# v2_1_Main.net
KiCad netlist of a schematic drawn in EAGLE
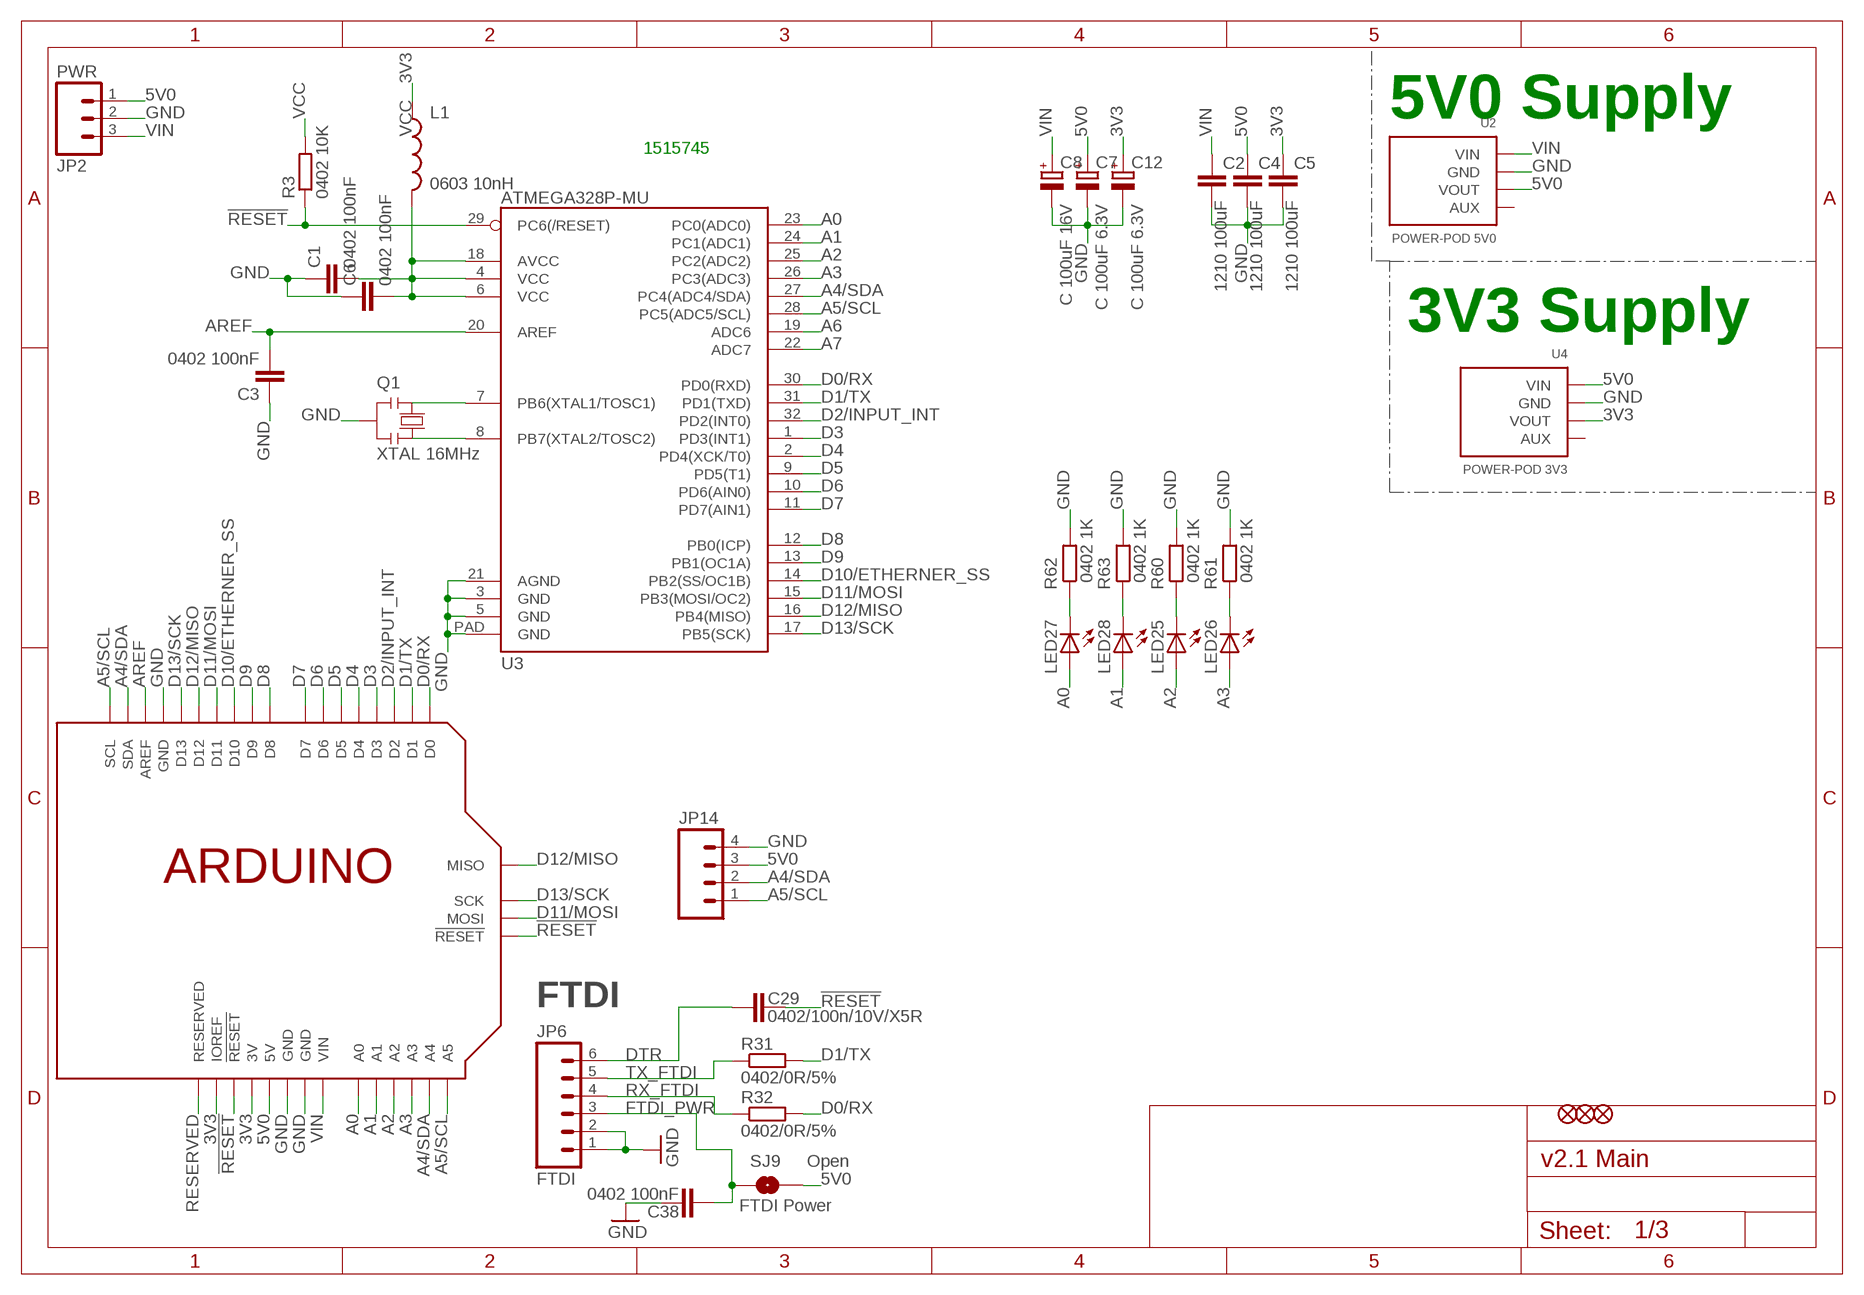
[diagram p0: schematic, sheet 1]
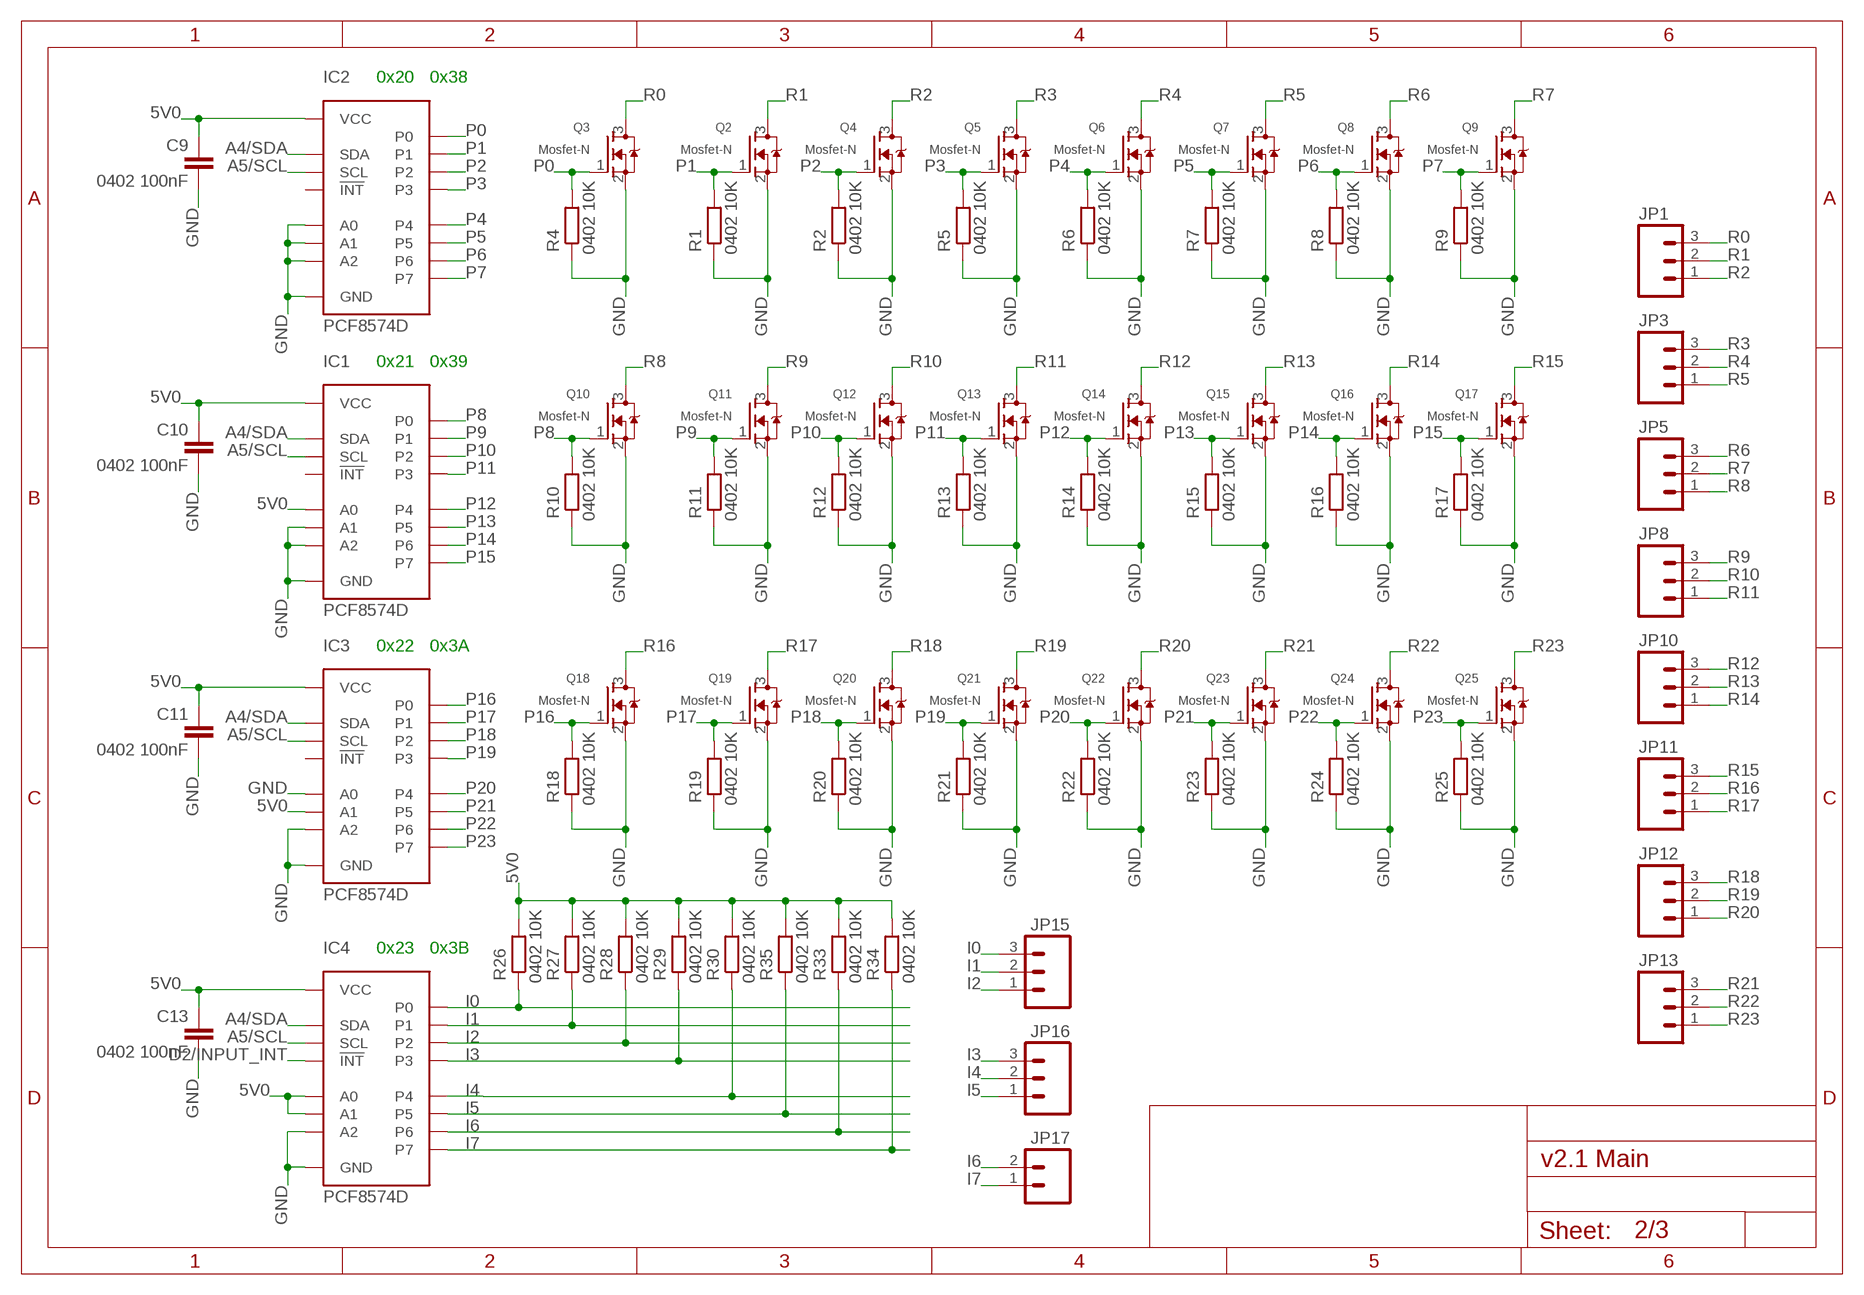
[diagram p1: schematic, sheet 2]
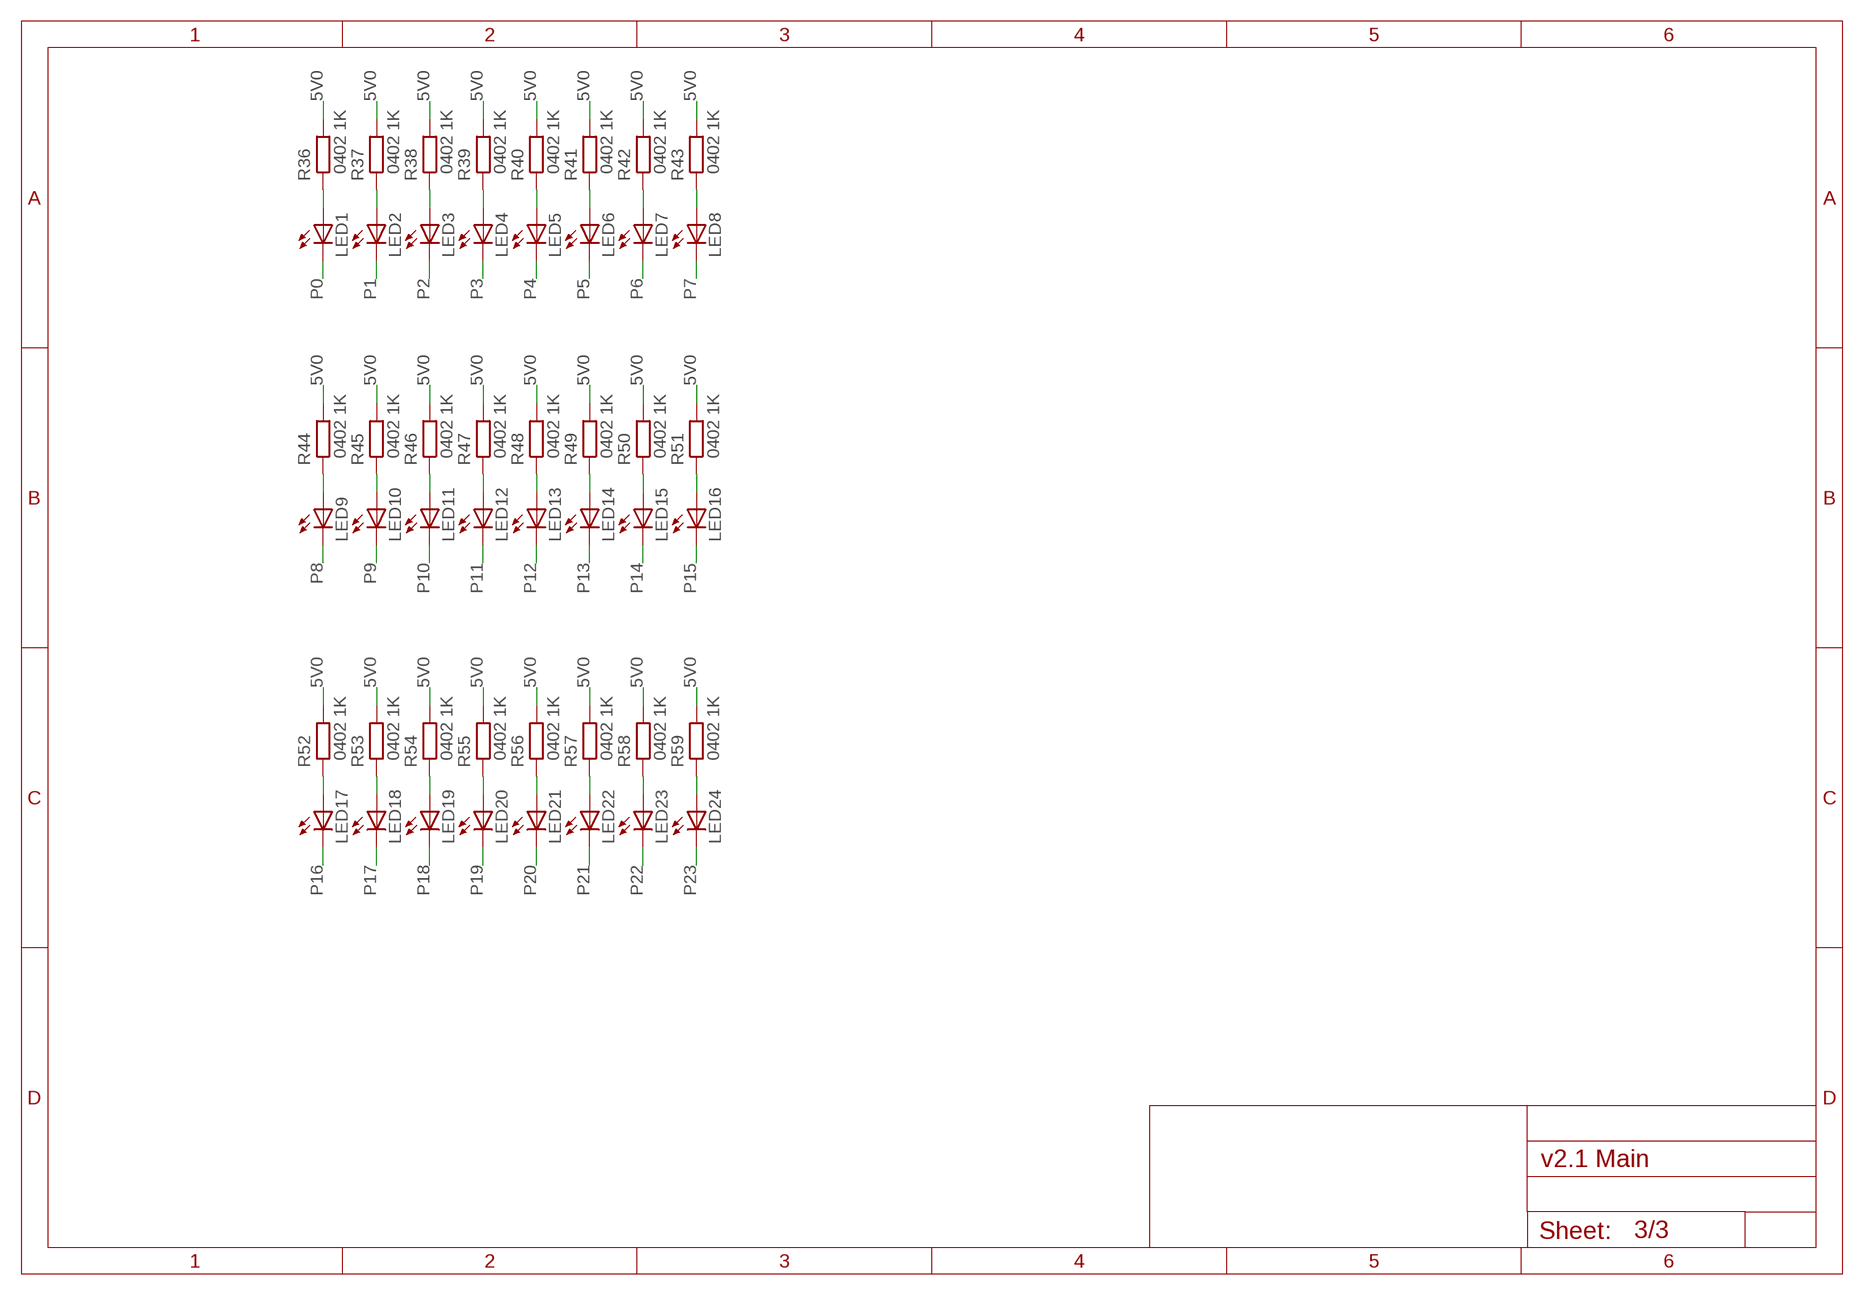
[diagram p2: schematic, sheet 3]

(export (version "E")
  (design (tool "Eeschema 10.0.6"))
  (components
    (comp (ref "LED1")
      (value "LED0805-1206")
      (footprint "eagle-import:LED-0805-1206")
      (libsource (lib "eagle-import") (part "LED0805-1206"))
    )
    (comp (ref "LED2")
      (value "LED0805-1206")
      (footprint "eagle-import:LED-0805-1206")
      (libsource (lib "eagle-import") (part "LED0805-1206"))
    )
    (comp (ref "LED3")
      (value "LED0805-1206")
      (footprint "eagle-import:LED-0805-1206")
      (libsource (lib "eagle-import") (part "LED0805-1206"))
    )
    (comp (ref "LED4")
      (value "LED0805-1206")
      (footprint "eagle-import:LED-0805-1206")
      (libsource (lib "eagle-import") (part "LED0805-1206"))
    )
    (comp (ref "LED5")
      (value "LED0805-1206")
      (footprint "eagle-import:LED-0805-1206")
      (libsource (lib "eagle-import") (part "LED0805-1206"))
    )
    (comp (ref "LED6")
      (value "LED0805-1206")
      (footprint "eagle-import:LED-0805-1206")
      (libsource (lib "eagle-import") (part "LED0805-1206"))
    )
    (comp (ref "LED7")
      (value "LED0805-1206")
      (footprint "eagle-import:LED-0805-1206")
      (libsource (lib "eagle-import") (part "LED0805-1206"))
    )
    (comp (ref "LED8")
      (value "LED0805-1206")
      (footprint "eagle-import:LED-0805-1206")
      (libsource (lib "eagle-import") (part "LED0805-1206"))
    )
    (comp (ref "LED9")
      (value "LED0805-1206")
      (footprint "eagle-import:LED-0805-1206")
      (libsource (lib "eagle-import") (part "LED0805-1206"))
    )
    (comp (ref "LED10")
      (value "LED0805-1206")
      (footprint "eagle-import:LED-0805-1206")
      (libsource (lib "eagle-import") (part "LED0805-1206"))
    )
    (comp (ref "LED11")
      (value "LED0805-1206")
      (footprint "eagle-import:LED-0805-1206")
      (libsource (lib "eagle-import") (part "LED0805-1206"))
    )
    (comp (ref "LED12")
      (value "LED0805-1206")
      (footprint "eagle-import:LED-0805-1206")
      (libsource (lib "eagle-import") (part "LED0805-1206"))
    )
    (comp (ref "LED13")
      (value "LED0805-1206")
      (footprint "eagle-import:LED-0805-1206")
      (libsource (lib "eagle-import") (part "LED0805-1206"))
    )
    (comp (ref "LED14")
      (value "LED0805-1206")
      (footprint "eagle-import:LED-0805-1206")
      (libsource (lib "eagle-import") (part "LED0805-1206"))
    )
    (comp (ref "LED15")
      (value "LED0805-1206")
      (footprint "eagle-import:LED-0805-1206")
      (libsource (lib "eagle-import") (part "LED0805-1206"))
    )
    (comp (ref "LED16")
      (value "LED0805-1206")
      (footprint "eagle-import:LED-0805-1206")
      (libsource (lib "eagle-import") (part "LED0805-1206"))
    )
    (comp (ref "LED17")
      (value "LED0805-1206")
      (footprint "eagle-import:LED-0805-1206")
      (libsource (lib "eagle-import") (part "LED0805-1206"))
    )
    (comp (ref "LED18")
      (value "LED0805-1206")
      (footprint "eagle-import:LED-0805-1206")
      (libsource (lib "eagle-import") (part "LED0805-1206"))
    )
    (comp (ref "LED19")
      (value "LED0805-1206")
      (footprint "eagle-import:LED-0805-1206")
      (libsource (lib "eagle-import") (part "LED0805-1206"))
    )
    (comp (ref "LED20")
      (value "LED0805-1206")
      (footprint "eagle-import:LED-0805-1206")
      (libsource (lib "eagle-import") (part "LED0805-1206"))
    )
    (comp (ref "LED21")
      (value "LED0805-1206")
      (footprint "eagle-import:LED-0805-1206")
      (libsource (lib "eagle-import") (part "LED0805-1206"))
    )
    (comp (ref "LED22")
      (value "LED0805-1206")
      (footprint "eagle-import:LED-0805-1206")
      (libsource (lib "eagle-import") (part "LED0805-1206"))
    )
    (comp (ref "LED23")
      (value "LED0805-1206")
      (footprint "eagle-import:LED-0805-1206")
      (libsource (lib "eagle-import") (part "LED0805-1206"))
    )
    (comp (ref "LED24")
      (value "LED0805-1206")
      (footprint "eagle-import:LED-0805-1206")
      (libsource (lib "eagle-import") (part "LED0805-1206"))
    )
    (comp (ref "R36")
      (value "0402 1K")
      (footprint "eagle-import:R0402-SMALLER")
      (libsource (lib "eagle-import") (part "R-EU_R0402-SMALLER"))
    )
    (comp (ref "R37")
      (value "0402 1K")
      (footprint "eagle-import:R0402-SMALLER")
      (libsource (lib "eagle-import") (part "R-EU_R0402-SMALLER"))
    )
    (comp (ref "R38")
      (value "0402 1K")
      (footprint "eagle-import:R0402-SMALLER")
      (libsource (lib "eagle-import") (part "R-EU_R0402-SMALLER"))
    )
    (comp (ref "R39")
      (value "0402 1K")
      (footprint "eagle-import:R0402-SMALLER")
      (libsource (lib "eagle-import") (part "R-EU_R0402-SMALLER"))
    )
    (comp (ref "R40")
      (value "0402 1K")
      (footprint "eagle-import:R0402-SMALLER")
      (libsource (lib "eagle-import") (part "R-EU_R0402-SMALLER"))
    )
    (comp (ref "R41")
      (value "0402 1K")
      (footprint "eagle-import:R0402-SMALLER")
      (libsource (lib "eagle-import") (part "R-EU_R0402-SMALLER"))
    )
    (comp (ref "R42")
      (value "0402 1K")
      (footprint "eagle-import:R0402-SMALLER")
      (libsource (lib "eagle-import") (part "R-EU_R0402-SMALLER"))
    )
    (comp (ref "R43")
      (value "0402 1K")
      (footprint "eagle-import:R0402-SMALLER")
      (libsource (lib "eagle-import") (part "R-EU_R0402-SMALLER"))
    )
    (comp (ref "R44")
      (value "0402 1K")
      (footprint "eagle-import:R0402-SMALLER")
      (libsource (lib "eagle-import") (part "R-EU_R0402-SMALLER"))
    )
    (comp (ref "R45")
      (value "0402 1K")
      (footprint "eagle-import:R0402-SMALLER")
      (libsource (lib "eagle-import") (part "R-EU_R0402-SMALLER"))
    )
    (comp (ref "R46")
      (value "0402 1K")
      (footprint "eagle-import:R0402-SMALLER")
      (libsource (lib "eagle-import") (part "R-EU_R0402-SMALLER"))
    )
    (comp (ref "R47")
      (value "0402 1K")
      (footprint "eagle-import:R0402-SMALLER")
      (libsource (lib "eagle-import") (part "R-EU_R0402-SMALLER"))
    )
    (comp (ref "R48")
      (value "0402 1K")
      (footprint "eagle-import:R0402-SMALLER")
      (libsource (lib "eagle-import") (part "R-EU_R0402-SMALLER"))
    )
    (comp (ref "R49")
      (value "0402 1K")
      (footprint "eagle-import:R0402-SMALLER")
      (libsource (lib "eagle-import") (part "R-EU_R0402-SMALLER"))
    )
    (comp (ref "R50")
      (value "0402 1K")
      (footprint "eagle-import:R0402-SMALLER")
      (libsource (lib "eagle-import") (part "R-EU_R0402-SMALLER"))
    )
    (comp (ref "R51")
      (value "0402 1K")
      (footprint "eagle-import:R0402-SMALLER")
      (libsource (lib "eagle-import") (part "R-EU_R0402-SMALLER"))
    )
    (comp (ref "R52")
      (value "0402 1K")
      (footprint "eagle-import:R0402-SMALLER")
      (libsource (lib "eagle-import") (part "R-EU_R0402-SMALLER"))
    )
    (comp (ref "R53")
      (value "0402 1K")
      (footprint "eagle-import:R0402-SMALLER")
      (libsource (lib "eagle-import") (part "R-EU_R0402-SMALLER"))
    )
    (comp (ref "R54")
      (value "0402 1K")
      (footprint "eagle-import:R0402-SMALLER")
      (libsource (lib "eagle-import") (part "R-EU_R0402-SMALLER"))
    )
    (comp (ref "R55")
      (value "0402 1K")
      (footprint "eagle-import:R0402-SMALLER")
      (libsource (lib "eagle-import") (part "R-EU_R0402-SMALLER"))
    )
    (comp (ref "R56")
      (value "0402 1K")
      (footprint "eagle-import:R0402-SMALLER")
      (libsource (lib "eagle-import") (part "R-EU_R0402-SMALLER"))
    )
    (comp (ref "R57")
      (value "0402 1K")
      (footprint "eagle-import:R0402-SMALLER")
      (libsource (lib "eagle-import") (part "R-EU_R0402-SMALLER"))
    )
    (comp (ref "R58")
      (value "0402 1K")
      (footprint "eagle-import:R0402-SMALLER")
      (libsource (lib "eagle-import") (part "R-EU_R0402-SMALLER"))
    )
    (comp (ref "R59")
      (value "0402 1K")
      (footprint "eagle-import:R0402-SMALLER")
      (libsource (lib "eagle-import") (part "R-EU_R0402-SMALLER"))
    )
    (comp (ref "C9")
      (value "0402 100nF")
      (footprint "eagle-import:C0402-SMALLER")
      (libsource (lib "eagle-import") (part "C-EUC0402-SMALLER"))
    )
    (comp (ref "C10")
      (value "0402 100nF")
      (footprint "eagle-import:C0402-SMALLER")
      (libsource (lib "eagle-import") (part "C-EUC0402-SMALLER"))
    )
    (comp (ref "C11")
      (value "0402 100nF")
      (footprint "eagle-import:C0402-SMALLER")
      (libsource (lib "eagle-import") (part "C-EUC0402-SMALLER"))
    )
    (comp (ref "C13")
      (value "0402 100nF")
      (footprint "eagle-import:C0402-SMALLER")
      (libsource (lib "eagle-import") (part "C-EUC0402-SMALLER"))
    )
    (comp (ref "IC1")
      (value "PCF8574D")
      (footprint "eagle-import:SO16-7.5MM")
      (libsource (lib "eagle-import") (part "PCF8574SO16-7/5MM"))
    )
    (comp (ref "IC2")
      (value "PCF8574D")
      (footprint "eagle-import:SO16-7.5MM")
      (libsource (lib "eagle-import") (part "PCF8574SO16-7/5MM"))
    )
    (comp (ref "IC3")
      (value "PCF8574D")
      (footprint "eagle-import:SO16-7.5MM")
      (libsource (lib "eagle-import") (part "PCF8574SO16-7/5MM"))
    )
    (comp (ref "IC4")
      (value "PCF8574D")
      (footprint "eagle-import:SO16-7.5MM")
      (libsource (lib "eagle-import") (part "PCF8574SO16-7/5MM"))
    )
    (comp (ref "JP1")
      (value "M03-SCREW-5MM")
      (footprint "eagle-import:SCREWTERMINAL-5MM-3")
      (libsource (lib "eagle-import") (part "M03-SCREW-5MM"))
    )
    (comp (ref "JP3")
      (value "M03-SCREW-5MM")
      (footprint "eagle-import:SCREWTERMINAL-5MM-3")
      (libsource (lib "eagle-import") (part "M03-SCREW-5MM"))
    )
    (comp (ref "JP5")
      (value "M03-SCREW-5MM")
      (footprint "eagle-import:SCREWTERMINAL-5MM-3")
      (libsource (lib "eagle-import") (part "M03-SCREW-5MM"))
    )
    (comp (ref "JP8")
      (value "M03-SCREW-5MM")
      (footprint "eagle-import:SCREWTERMINAL-5MM-3")
      (libsource (lib "eagle-import") (part "M03-SCREW-5MM"))
    )
    (comp (ref "JP10")
      (value "M03-SCREW-5MM")
      (footprint "eagle-import:SCREWTERMINAL-5MM-3")
      (libsource (lib "eagle-import") (part "M03-SCREW-5MM"))
    )
    (comp (ref "JP11")
      (value "M03-SCREW-5MM")
      (footprint "eagle-import:SCREWTERMINAL-5MM-3")
      (libsource (lib "eagle-import") (part "M03-SCREW-5MM"))
    )
    (comp (ref "JP12")
      (value "M03-SCREW-5MM")
      (footprint "eagle-import:SCREWTERMINAL-5MM-3")
      (libsource (lib "eagle-import") (part "M03-SCREW-5MM"))
    )
    (comp (ref "JP13")
      (value "M03-SCREW-5MM")
      (footprint "eagle-import:SCREWTERMINAL-5MM-3")
      (libsource (lib "eagle-import") (part "M03-SCREW-5MM"))
    )
    (comp (ref "JP15")
      (value "M03-SCREW-5MM")
      (footprint "eagle-import:SCREWTERMINAL-5MM-3")
      (libsource (lib "eagle-import") (part "M03-SCREW-5MM"))
    )
    (comp (ref "JP16")
      (value "M03-SCREW-5MM")
      (footprint "eagle-import:SCREWTERMINAL-5MM-3")
      (libsource (lib "eagle-import") (part "M03-SCREW-5MM"))
    )
    (comp (ref "JP17")
      (value "M025MM")
      (footprint "eagle-import:SCREWTERMINAL-5MM-2")
      (libsource (lib "eagle-import") (part "M025MM"))
    )
    (comp (ref "Q2")
      (value "Mosfet-N")
      (footprint "eagle-import:SOT23-3")
      (libsource (lib "eagle-import") (part "MOSFET-N-SOT23-SPARK"))
    )
    (comp (ref "Q3")
      (value "Mosfet-N")
      (footprint "eagle-import:SOT23-3")
      (libsource (lib "eagle-import") (part "MOSFET-N-SOT23-SPARK"))
    )
    (comp (ref "Q4")
      (value "Mosfet-N")
      (footprint "eagle-import:SOT23-3")
      (libsource (lib "eagle-import") (part "MOSFET-N-SOT23-SPARK"))
    )
    (comp (ref "Q5")
      (value "Mosfet-N")
      (footprint "eagle-import:SOT23-3")
      (libsource (lib "eagle-import") (part "MOSFET-N-SOT23-SPARK"))
    )
    (comp (ref "Q6")
      (value "Mosfet-N")
      (footprint "eagle-import:SOT23-3")
      (libsource (lib "eagle-import") (part "MOSFET-N-SOT23-SPARK"))
    )
    (comp (ref "Q7")
      (value "Mosfet-N")
      (footprint "eagle-import:SOT23-3")
      (libsource (lib "eagle-import") (part "MOSFET-N-SOT23-SPARK"))
    )
    (comp (ref "Q8")
      (value "Mosfet-N")
      (footprint "eagle-import:SOT23-3")
      (libsource (lib "eagle-import") (part "MOSFET-N-SOT23-SPARK"))
    )
    (comp (ref "Q9")
      (value "Mosfet-N")
      (footprint "eagle-import:SOT23-3")
      (libsource (lib "eagle-import") (part "MOSFET-N-SOT23-SPARK"))
    )
    (comp (ref "Q10")
      (value "Mosfet-N")
      (footprint "eagle-import:SOT23-3")
      (libsource (lib "eagle-import") (part "MOSFET-N-SOT23-SPARK"))
    )
    (comp (ref "Q11")
      (value "Mosfet-N")
      (footprint "eagle-import:SOT23-3")
      (libsource (lib "eagle-import") (part "MOSFET-N-SOT23-SPARK"))
    )
    (comp (ref "Q12")
      (value "Mosfet-N")
      (footprint "eagle-import:SOT23-3")
      (libsource (lib "eagle-import") (part "MOSFET-N-SOT23-SPARK"))
    )
    (comp (ref "Q13")
      (value "Mosfet-N")
      (footprint "eagle-import:SOT23-3")
      (libsource (lib "eagle-import") (part "MOSFET-N-SOT23-SPARK"))
    )
    (comp (ref "Q14")
      (value "Mosfet-N")
      (footprint "eagle-import:SOT23-3")
      (libsource (lib "eagle-import") (part "MOSFET-N-SOT23-SPARK"))
    )
    (comp (ref "Q15")
      (value "Mosfet-N")
      (footprint "eagle-import:SOT23-3")
      (libsource (lib "eagle-import") (part "MOSFET-N-SOT23-SPARK"))
    )
    (comp (ref "Q16")
      (value "Mosfet-N")
      (footprint "eagle-import:SOT23-3")
      (libsource (lib "eagle-import") (part "MOSFET-N-SOT23-SPARK"))
    )
    (comp (ref "Q17")
      (value "Mosfet-N")
      (footprint "eagle-import:SOT23-3")
      (libsource (lib "eagle-import") (part "MOSFET-N-SOT23-SPARK"))
    )
    (comp (ref "Q18")
      (value "Mosfet-N")
      (footprint "eagle-import:SOT23-3")
      (libsource (lib "eagle-import") (part "MOSFET-N-SOT23-SPARK"))
    )
    (comp (ref "Q19")
      (value "Mosfet-N")
      (footprint "eagle-import:SOT23-3")
      (libsource (lib "eagle-import") (part "MOSFET-N-SOT23-SPARK"))
    )
    (comp (ref "Q20")
      (value "Mosfet-N")
      (footprint "eagle-import:SOT23-3")
      (libsource (lib "eagle-import") (part "MOSFET-N-SOT23-SPARK"))
    )
    (comp (ref "Q21")
      (value "Mosfet-N")
      (footprint "eagle-import:SOT23-3")
      (libsource (lib "eagle-import") (part "MOSFET-N-SOT23-SPARK"))
    )
    (comp (ref "Q22")
      (value "Mosfet-N")
      (footprint "eagle-import:SOT23-3")
      (libsource (lib "eagle-import") (part "MOSFET-N-SOT23-SPARK"))
    )
    (comp (ref "Q23")
      (value "Mosfet-N")
      (footprint "eagle-import:SOT23-3")
      (libsource (lib "eagle-import") (part "MOSFET-N-SOT23-SPARK"))
    )
    (comp (ref "Q24")
      (value "Mosfet-N")
      (footprint "eagle-import:SOT23-3")
      (libsource (lib "eagle-import") (part "MOSFET-N-SOT23-SPARK"))
    )
    (comp (ref "Q25")
      (value "Mosfet-N")
      (footprint "eagle-import:SOT23-3")
      (libsource (lib "eagle-import") (part "MOSFET-N-SOT23-SPARK"))
    )
    (comp (ref "R1")
      (value "0402 10K")
      (footprint "eagle-import:R0402-SMALLER")
      (libsource (lib "eagle-import") (part "R-EU_R0402-SMALLER"))
    )
    (comp (ref "R2")
      (value "0402 10K")
      (footprint "eagle-import:R0402-SMALLER")
      (libsource (lib "eagle-import") (part "R-EU_R0402-SMALLER"))
    )
    (comp (ref "R4")
      (value "0402 10K")
      (footprint "eagle-import:R0402-SMALLER")
      (libsource (lib "eagle-import") (part "R-EU_R0402-SMALLER"))
    )
    (comp (ref "R5")
      (value "0402 10K")
      (footprint "eagle-import:R0402-SMALLER")
      (libsource (lib "eagle-import") (part "R-EU_R0402-SMALLER"))
    )
    (comp (ref "R6")
      (value "0402 10K")
      (footprint "eagle-import:R0402-SMALLER")
      (libsource (lib "eagle-import") (part "R-EU_R0402-SMALLER"))
    )
    (comp (ref "R7")
      (value "0402 10K")
      (footprint "eagle-import:R0402-SMALLER")
      (libsource (lib "eagle-import") (part "R-EU_R0402-SMALLER"))
    )
    (comp (ref "R8")
      (value "0402 10K")
      (footprint "eagle-import:R0402-SMALLER")
      (libsource (lib "eagle-import") (part "R-EU_R0402-SMALLER"))
    )
    (comp (ref "R9")
      (value "0402 10K")
      (footprint "eagle-import:R0402-SMALLER")
      (libsource (lib "eagle-import") (part "R-EU_R0402-SMALLER"))
    )
    (comp (ref "R10")
      (value "0402 10K")
      (footprint "eagle-import:R0402-SMALLER")
      (libsource (lib "eagle-import") (part "R-EU_R0402-SMALLER"))
    )
    (comp (ref "R11")
      (value "0402 10K")
      (footprint "eagle-import:R0402-SMALLER")
      (libsource (lib "eagle-import") (part "R-EU_R0402-SMALLER"))
    )
    (comp (ref "R12")
      (value "0402 10K")
      (footprint "eagle-import:R0402-SMALLER")
      (libsource (lib "eagle-import") (part "R-EU_R0402-SMALLER"))
    )
    (comp (ref "R13")
      (value "0402 10K")
      (footprint "eagle-import:R0402-SMALLER")
      (libsource (lib "eagle-import") (part "R-EU_R0402-SMALLER"))
    )
    (comp (ref "R14")
      (value "0402 10K")
      (footprint "eagle-import:R0402-SMALLER")
      (libsource (lib "eagle-import") (part "R-EU_R0402-SMALLER"))
    )
    (comp (ref "R15")
      (value "0402 10K")
      (footprint "eagle-import:R0402-SMALLER")
      (libsource (lib "eagle-import") (part "R-EU_R0402-SMALLER"))
    )
    (comp (ref "R16")
      (value "0402 10K")
      (footprint "eagle-import:R0402-SMALLER")
      (libsource (lib "eagle-import") (part "R-EU_R0402-SMALLER"))
    )
    (comp (ref "R17")
      (value "0402 10K")
      (footprint "eagle-import:R0402-SMALLER")
      (libsource (lib "eagle-import") (part "R-EU_R0402-SMALLER"))
    )
    (comp (ref "R18")
      (value "0402 10K")
      (footprint "eagle-import:R0402-SMALLER")
      (libsource (lib "eagle-import") (part "R-EU_R0402-SMALLER"))
    )
    (comp (ref "R19")
      (value "0402 10K")
      (footprint "eagle-import:R0402-SMALLER")
      (libsource (lib "eagle-import") (part "R-EU_R0402-SMALLER"))
    )
    (comp (ref "R20")
      (value "0402 10K")
      (footprint "eagle-import:R0402-SMALLER")
      (libsource (lib "eagle-import") (part "R-EU_R0402-SMALLER"))
    )
    (comp (ref "R21")
      (value "0402 10K")
      (footprint "eagle-import:R0402-SMALLER")
      (libsource (lib "eagle-import") (part "R-EU_R0402-SMALLER"))
    )
    (comp (ref "R22")
      (value "0402 10K")
      (footprint "eagle-import:R0402-SMALLER")
      (libsource (lib "eagle-import") (part "R-EU_R0402-SMALLER"))
    )
    (comp (ref "R23")
      (value "0402 10K")
      (footprint "eagle-import:R0402-SMALLER")
      (libsource (lib "eagle-import") (part "R-EU_R0402-SMALLER"))
    )
    (comp (ref "R24")
      (value "0402 10K")
      (footprint "eagle-import:R0402-SMALLER")
      (libsource (lib "eagle-import") (part "R-EU_R0402-SMALLER"))
    )
    (comp (ref "R25")
      (value "0402 10K")
      (footprint "eagle-import:R0402-SMALLER")
      (libsource (lib "eagle-import") (part "R-EU_R0402-SMALLER"))
    )
    (comp (ref "R26")
      (value "0402 10K")
      (footprint "eagle-import:R0402-SMALLER")
      (libsource (lib "eagle-import") (part "R-EU_R0402-SMALLER"))
    )
    (comp (ref "R27")
      (value "0402 10K")
      (footprint "eagle-import:R0402-SMALLER")
      (libsource (lib "eagle-import") (part "R-EU_R0402-SMALLER"))
    )
    (comp (ref "R28")
      (value "0402 10K")
      (footprint "eagle-import:R0402-SMALLER")
      (libsource (lib "eagle-import") (part "R-EU_R0402-SMALLER"))
    )
    (comp (ref "R29")
      (value "0402 10K")
      (footprint "eagle-import:R0402-SMALLER")
      (libsource (lib "eagle-import") (part "R-EU_R0402-SMALLER"))
    )
    (comp (ref "R30")
      (value "0402 10K")
      (footprint "eagle-import:R0402-SMALLER")
      (libsource (lib "eagle-import") (part "R-EU_R0402-SMALLER"))
    )
    (comp (ref "R33")
      (value "0402 10K")
      (footprint "eagle-import:R0402-SMALLER")
      (libsource (lib "eagle-import") (part "R-EU_R0402-SMALLER"))
    )
    (comp (ref "R34")
      (value "0402 10K")
      (footprint "eagle-import:R0402-SMALLER")
      (libsource (lib "eagle-import") (part "R-EU_R0402-SMALLER"))
    )
    (comp (ref "R35")
      (value "0402 10K")
      (footprint "eagle-import:R0402-SMALLER")
      (libsource (lib "eagle-import") (part "R-EU_R0402-SMALLER"))
    )
    (comp (ref "C1")
      (value "0402 100nF")
      (footprint "eagle-import:C0402-SMALLER")
      (libsource (lib "eagle-import") (part "C-EUC0402-SMALLER"))
    )
    (comp (ref "C2")
      (value "1210 100uF")
      (footprint "eagle-import:C1210")
      (libsource (lib "eagle-import") (part "C-EUC1210"))
    )
    (comp (ref "C3")
      (value "0402 100nF")
      (footprint "eagle-import:C0402-SMALLER")
      (libsource (lib "eagle-import") (part "C-EUC0402-SMALLER"))
    )
    (comp (ref "C4")
      (value "1210 100uF")
      (footprint "eagle-import:C1210")
      (libsource (lib "eagle-import") (part "C-EUC1210"))
    )
    (comp (ref "C5")
      (value "1210 100uF")
      (footprint "eagle-import:C1210")
      (libsource (lib "eagle-import") (part "C-EUC1210"))
    )
    (comp (ref "C6")
      (value "0402 100nF")
      (footprint "eagle-import:C0402-SMALLER")
      (libsource (lib "eagle-import") (part "C-EUC0402-SMALLER"))
    )
    (comp (ref "C7")
      (value "C 100uF 6.3V")
      (footprint "eagle-import:PANASONIC_C")
      (libsource (lib "eagle-import") (part "CPOL-EUC"))
    )
    (comp (ref "C8")
      (value "C 100uF 16V")
      (footprint "eagle-import:PANASONIC_C")
      (libsource (lib "eagle-import") (part "CPOL-EUC"))
    )
    (comp (ref "C12")
      (value "C 100uF 6.3V")
      (footprint "eagle-import:PANASONIC_C")
      (libsource (lib "eagle-import") (part "CPOL-EUC"))
    )
    (comp (ref "C29")
      (value "0402/100n/10V/X5R")
      (footprint "eagle-import:C0402-ARDUINO-ROUND")
      (libsource (lib "eagle-import") (part "TiLDA Mk2 Parts_C-EUC0402-ARDUINO-ROUND"))
    )
    (comp (ref "C38")
      (value "0402 100nF")
      (footprint "eagle-import:C0402-SMALLER")
      (libsource (lib "eagle-import") (part "TiLDA Mk2 Parts_C-EUC0402-SMALLER"))
    )
    (comp (ref "JP2")
      (value "PWR")
      (footprint "eagle-import:SCREWTERMINAL-5MM-3")
      (libsource (lib "eagle-import") (part "M03-SCREW-5MM"))
    )
    (comp (ref "JP4")
      (value "FIDUCIAL1X2.5-STOP")
      (footprint "eagle-import:FIDUCIAL-1X2.5-STOP")
      (libsource (lib "eagle-import") (part "FIDUCIAL1X2.5-STOP"))
    )
    (comp (ref "JP6")
      (value "FTDI")
      (footprint "eagle-import:1X06")
      (libsource (lib "eagle-import") (part "M06SIP"))
    )
    (comp (ref "JP7")
      (value "FIDUCIAL1X2.5-STOP")
      (footprint "eagle-import:FIDUCIAL-1X2.5-STOP")
      (libsource (lib "eagle-import") (part "FIDUCIAL1X2.5-STOP"))
    )
    (comp (ref "JP9")
      (value "FIDUCIAL1X2.5-STOP")
      (footprint "eagle-import:FIDUCIAL-1X2.5-STOP")
      (libsource (lib "eagle-import") (part "FIDUCIAL1X2.5-STOP"))
    )
    (comp (ref "JP14")
      (value "M04PTH")
      (footprint "eagle-import:1X04")
      (libsource (lib "eagle-import") (part "M04PTH"))
    )
    (comp (ref "L1")
      (value "0603 10nH")
      (footprint "eagle-import:C0603K-SMALL")
      (libsource (lib "eagle-import") (part "INDUCTOR0603K-SMALL"))
    )
    (comp (ref "LED25")
      (value "LED0805-1206")
      (footprint "eagle-import:LED-0805-1206")
      (libsource (lib "eagle-import") (part "LED0805-1206"))
    )
    (comp (ref "LED26")
      (value "LED0805-1206")
      (footprint "eagle-import:LED-0805-1206")
      (libsource (lib "eagle-import") (part "LED0805-1206"))
    )
    (comp (ref "LED27")
      (value "LED0805-1206")
      (footprint "eagle-import:LED-0805-1206")
      (libsource (lib "eagle-import") (part "LED0805-1206"))
    )
    (comp (ref "LED28")
      (value "LED0805-1206")
      (footprint "eagle-import:LED-0805-1206")
      (libsource (lib "eagle-import") (part "LED0805-1206"))
    )
    (comp (ref "Q1")
      (value "XTAL 16MHz")
      (footprint "eagle-import:RESONATOR")
      (libsource (lib "eagle-import") (part "RESONATORMU"))
    )
    (comp (ref "R3")
      (value "0402 10K")
      (footprint "eagle-import:R0402-SMALLER")
      (libsource (lib "eagle-import") (part "R-EU_R0402-SMALLER"))
    )
    (comp (ref "R31")
      (value "0402/0R/5%")
      (footprint "eagle-import:R0402-ARDUINO-ROUND")
      (libsource (lib "eagle-import") (part "TiLDA Mk2 Parts_R-EU_R0402-ARDUINO-ROUND"))
    )
    (comp (ref "R32")
      (value "0402/0R/5%")
      (footprint "eagle-import:R0402-ARDUINO-ROUND")
      (libsource (lib "eagle-import") (part "TiLDA Mk2 Parts_R-EU_R0402-ARDUINO-ROUND"))
    )
    (comp (ref "R60")
      (value "0402 1K")
      (footprint "eagle-import:R0402-SMALLER")
      (libsource (lib "eagle-import") (part "R-EU_R0402-SMALLER"))
    )
    (comp (ref "R61")
      (value "0402 1K")
      (footprint "eagle-import:R0402-SMALLER")
      (libsource (lib "eagle-import") (part "R-EU_R0402-SMALLER"))
    )
    (comp (ref "R62")
      (value "0402 1K")
      (footprint "eagle-import:R0402-SMALLER")
      (libsource (lib "eagle-import") (part "R-EU_R0402-SMALLER"))
    )
    (comp (ref "R63")
      (value "0402 1K")
      (footprint "eagle-import:R0402-SMALLER")
      (libsource (lib "eagle-import") (part "R-EU_R0402-SMALLER"))
    )
    (comp (ref "SJ9")
      (value "FTDI Power")
      (footprint "eagle-import:SJ_2S-TRACE")
      (libsource (lib "eagle-import") (part "SOLDERJUMPERTRACE"))
    )
    (comp (ref "U1")
      (value "ARDUINOSPI-REFRENCE")
      (footprint "eagle-import:ARDUINOR3-LWKTXT-REF-SPI")
      (libsource (lib "eagle-import") (part "ARDUINOSPI-REFRENCE"))
    )
    (comp (ref "U2")
      (value "POWER-POD 5V0")
      (footprint "eagle-import:POWER-POD-LANDING")
      (libsource (lib "eagle-import") (part "POWER-POD"))
    )
    (comp (ref "U3")
      (value "ATMEGA328P-MU")
      (footprint "eagle-import:MLF32-SHORT-CREAM")
      (libsource (lib "eagle-import") (part "ATMEGA328-MLF-SHORT"))
    )
    (comp (ref "U4")
      (value "POWER-POD 3V3")
      (footprint "eagle-import:POWER-POD-LANDING")
      (libsource (lib "eagle-import") (part "POWER-POD"))
    )
  )
  (nets
    (net (code "1") (name "3V3") (class "Default")
      (node (ref "C12") (pin "+") (pinfunction "+_+") (pintype "passive"))
      (node (ref "C5") (pin "1") (pinfunction "1_1") (pintype "passive"))
      (node (ref "L1") (pin "1") (pinfunction "1_1") (pintype "passive"))
      (node (ref "U1") (pin "3V") (pinfunction "3V_3V") (pintype "power_in"))
      (node (ref "U1") (pin "IOREF") (pinfunction "IOREF_IOREF") (pintype "output"))
      (node (ref "U4") (pin "3") (pinfunction "VOUT_3") (pintype "bidirectional"))
    )
    (net (code "2") (name "5V0") (class "Default")
      (node (ref "C10") (pin "1") (pinfunction "1_1") (pintype "passive"))
      (node (ref "C11") (pin "1") (pinfunction "1_1") (pintype "passive"))
      (node (ref "C13") (pin "1") (pinfunction "1_1") (pintype "passive"))
      (node (ref "C4") (pin "1") (pinfunction "1_1") (pintype "passive"))
      (node (ref "C7") (pin "+") (pinfunction "+_+") (pintype "passive"))
      (node (ref "C9") (pin "1") (pinfunction "1_1") (pintype "passive"))
      (node (ref "IC1") (pin "1") (pinfunction "A0_1") (pintype "bidirectional"))
      (node (ref "IC1") (pin "16") (pinfunction "VCC_16") (pintype "bidirectional"))
      (node (ref "IC2") (pin "16") (pinfunction "VCC_16") (pintype "bidirectional"))
      (node (ref "IC3") (pin "16") (pinfunction "VCC_16") (pintype "bidirectional"))
      (node (ref "IC3") (pin "2") (pinfunction "A1_2") (pintype "bidirectional"))
      (node (ref "IC4") (pin "1") (pinfunction "A0_1") (pintype "bidirectional"))
      (node (ref "IC4") (pin "16") (pinfunction "VCC_16") (pintype "bidirectional"))
      (node (ref "IC4") (pin "2") (pinfunction "A1_2") (pintype "bidirectional"))
      (node (ref "JP14") (pin "3") (pinfunction "3_3") (pintype "passive"))
      (node (ref "JP2") (pin "1") (pinfunction "1_1") (pintype "passive"))
      (node (ref "R26") (pin "2") (pinfunction "2_2") (pintype "passive"))
      (node (ref "R27") (pin "2") (pinfunction "2_2") (pintype "passive"))
      (node (ref "R28") (pin "2") (pinfunction "2_2") (pintype "passive"))
      (node (ref "R29") (pin "2") (pinfunction "2_2") (pintype "passive"))
      (node (ref "R30") (pin "2") (pinfunction "2_2") (pintype "passive"))
      (node (ref "R33") (pin "2") (pinfunction "2_2") (pintype "passive"))
      (node (ref "R34") (pin "2") (pinfunction "2_2") (pintype "passive"))
      (node (ref "R35") (pin "2") (pinfunction "2_2") (pintype "passive"))
      (node (ref "R36") (pin "2") (pinfunction "2_2") (pintype "passive"))
      (node (ref "R37") (pin "2") (pinfunction "2_2") (pintype "passive"))
      (node (ref "R38") (pin "2") (pinfunction "2_2") (pintype "passive"))
      (node (ref "R39") (pin "2") (pinfunction "2_2") (pintype "passive"))
      (node (ref "R40") (pin "2") (pinfunction "2_2") (pintype "passive"))
      (node (ref "R41") (pin "2") (pinfunction "2_2") (pintype "passive"))
      (node (ref "R42") (pin "2") (pinfunction "2_2") (pintype "passive"))
      (node (ref "R43") (pin "2") (pinfunction "2_2") (pintype "passive"))
      (node (ref "R44") (pin "2") (pinfunction "2_2") (pintype "passive"))
      (node (ref "R45") (pin "2") (pinfunction "2_2") (pintype "passive"))
      (node (ref "R46") (pin "2") (pinfunction "2_2") (pintype "passive"))
      (node (ref "R47") (pin "2") (pinfunction "2_2") (pintype "passive"))
      (node (ref "R48") (pin "2") (pinfunction "2_2") (pintype "passive"))
      (node (ref "R49") (pin "2") (pinfunction "2_2") (pintype "passive"))
      (node (ref "R50") (pin "2") (pinfunction "2_2") (pintype "passive"))
      (node (ref "R51") (pin "2") (pinfunction "2_2") (pintype "passive"))
      (node (ref "R52") (pin "2") (pinfunction "2_2") (pintype "passive"))
      (node (ref "R53") (pin "2") (pinfunction "2_2") (pintype "passive"))
      (node (ref "R54") (pin "2") (pinfunction "2_2") (pintype "passive"))
      (node (ref "R55") (pin "2") (pinfunction "2_2") (pintype "passive"))
      (node (ref "R56") (pin "2") (pinfunction "2_2") (pintype "passive"))
      (node (ref "R57") (pin "2") (pinfunction "2_2") (pintype "passive"))
      (node (ref "R58") (pin "2") (pinfunction "2_2") (pintype "passive"))
      (node (ref "R59") (pin "2") (pinfunction "2_2") (pintype "passive"))
      (node (ref "SJ9") (pin "2") (pinfunction "2_2") (pintype "passive"))
      (node (ref "U1") (pin "5V") (pinfunction "5V_5V") (pintype "power_in"))
      (node (ref "U1") (pin "5V@ISP") (pinfunction "5V_5V@ISP") (pintype "power_in"))
      (node (ref "U2") (pin "3") (pinfunction "VOUT_3") (pintype "bidirectional"))
      (node (ref "U4") (pin "1") (pinfunction "VIN_1") (pintype "bidirectional"))
    )
    (net (code "3") (name "A0") (class "Default")
      (node (ref "LED27") (pin "A") (pinfunction "A_A") (pintype "passive"))
      (node (ref "U1") (pin "A0") (pinfunction "A0_A0") (pintype "bidirectional"))
      (node (ref "U3") (pin "23") (pinfunction "PC0(ADC0)_23") (pintype "bidirectional"))
    )
    (net (code "4") (name "A1") (class "Default")
      (node (ref "LED28") (pin "A") (pinfunction "A_A") (pintype "passive"))
      (node (ref "U1") (pin "A1") (pinfunction "A1_A1") (pintype "bidirectional"))
      (node (ref "U3") (pin "24") (pinfunction "PC1(ADC1)_24") (pintype "bidirectional"))
    )
    (net (code "5") (name "A2") (class "Default")
      (node (ref "LED25") (pin "A") (pinfunction "A_A") (pintype "passive"))
      (node (ref "U1") (pin "A2") (pinfunction "A2_A2") (pintype "bidirectional"))
      (node (ref "U3") (pin "25") (pinfunction "PC2(ADC2)_25") (pintype "bidirectional"))
    )
    (net (code "6") (name "A3") (class "Default")
      (node (ref "LED26") (pin "A") (pinfunction "A_A") (pintype "passive"))
      (node (ref "U1") (pin "A3") (pinfunction "A3_A3") (pintype "bidirectional"))
      (node (ref "U3") (pin "26") (pinfunction "PC3(ADC3)_26") (pintype "bidirectional"))
    )
    (net (code "7") (name "A4{slash}SDA") (class "Default")
      (node (ref "IC1") (pin "15") (pinfunction "SDA_15") (pintype "bidirectional"))
      (node (ref "IC2") (pin "15") (pinfunction "SDA_15") (pintype "bidirectional"))
      (node (ref "IC3") (pin "15") (pinfunction "SDA_15") (pintype "bidirectional"))
      (node (ref "IC4") (pin "15") (pinfunction "SDA_15") (pintype "bidirectional"))
      (node (ref "JP14") (pin "2") (pinfunction "2_2") (pintype "passive"))
      (node (ref "U1") (pin "A4") (pinfunction "A4_A4") (pintype "bidirectional"))
      (node (ref "U1") (pin "SDA") (pinfunction "SDA_SDA") (pintype "bidirectional"))
      (node (ref "U3") (pin "27") (pinfunction "PC4(ADC4/SDA)_27") (pintype "bidirectional"))
    )
    (net (code "8") (name "A5{slash}SCL") (class "Default")
      (node (ref "IC1") (pin "14") (pinfunction "SCL_14") (pintype "bidirectional"))
      (node (ref "IC2") (pin "14") (pinfunction "SCL_14") (pintype "bidirectional"))
      (node (ref "IC3") (pin "14") (pinfunction "SCL_14") (pintype "bidirectional"))
      (node (ref "IC4") (pin "14") (pinfunction "SCL_14") (pintype "bidirectional"))
      (node (ref "JP14") (pin "1") (pinfunction "1_1") (pintype "passive"))
      (node (ref "U1") (pin "A5") (pinfunction "A5_A5") (pintype "bidirectional"))
      (node (ref "U1") (pin "SCL") (pinfunction "SCL_SCL") (pintype "bidirectional"))
      (node (ref "U3") (pin "28") (pinfunction "PC5(ADC5/SCL)_28") (pintype "bidirectional"))
    )
    (net (code "9") (name "A6") (class "Default")
      (node (ref "U3") (pin "19") (pinfunction "ADC6_19") (pintype "bidirectional"))
    )
    (net (code "10") (name "A7") (class "Default")
      (node (ref "U3") (pin "22") (pinfunction "ADC7_22") (pintype "bidirectional"))
    )
    (net (code "11") (name "AREF") (class "Default")
      (node (ref "C3") (pin "2") (pinfunction "2_2") (pintype "passive"))
      (node (ref "U1") (pin "AREF") (pinfunction "AREF_AREF") (pintype "bidirectional"))
      (node (ref "U3") (pin "20") (pinfunction "AREF_20") (pintype "bidirectional"))
    )
    (net (code "12") (name "D0{slash}RX") (class "Default")
      (node (ref "R32") (pin "2") (pinfunction "2_2") (pintype "passive"))
      (node (ref "U1") (pin "D0") (pinfunction "D0_D0") (pintype "bidirectional"))
      (node (ref "U3") (pin "30") (pinfunction "PD0(RXD)_30") (pintype "bidirectional"))
    )
    (net (code "13") (name "D1{slash}TX") (class "Default")
      (node (ref "R31") (pin "2") (pinfunction "2_2") (pintype "passive"))
      (node (ref "U1") (pin "D1") (pinfunction "D1_D1") (pintype "bidirectional"))
      (node (ref "U3") (pin "31") (pinfunction "PD1(TXD)_31") (pintype "bidirectional"))
    )
    (net (code "14") (name "D2{slash}INPUT_INT") (class "Default")
      (node (ref "IC4") (pin "13") (pinfunction "~{INT}_13") (pintype "bidirectional"))
      (node (ref "U1") (pin "D2") (pinfunction "D2_D2") (pintype "bidirectional"))
      (node (ref "U3") (pin "32") (pinfunction "PD2(INT0)_32") (pintype "bidirectional"))
    )
    (net (code "15") (name "D3") (class "Default")
      (node (ref "U1") (pin "D3") (pinfunction "D3_D3") (pintype "bidirectional"))
      (node (ref "U3") (pin "1") (pinfunction "PD3(INT1)_1") (pintype "bidirectional"))
    )
    (net (code "16") (name "D4") (class "Default")
      (node (ref "U1") (pin "D4") (pinfunction "D4_D4") (pintype "bidirectional"))
      (node (ref "U3") (pin "2") (pinfunction "PD4(XCK/T0)_2") (pintype "bidirectional"))
    )
    (net (code "17") (name "D5") (class "Default")
      (node (ref "U1") (pin "D5") (pinfunction "D5_D5") (pintype "bidirectional"))
      (node (ref "U3") (pin "9") (pinfunction "PD5(T1)_9") (pintype "bidirectional"))
    )
    (net (code "18") (name "D6") (class "Default")
      (node (ref "U1") (pin "D6") (pinfunction "D6_D6") (pintype "bidirectional"))
      (node (ref "U3") (pin "10") (pinfunction "PD6(AIN0)_10") (pintype "bidirectional"))
    )
    (net (code "19") (name "D7") (class "Default")
      (node (ref "U1") (pin "D7") (pinfunction "D7_D7") (pintype "bidirectional"))
      (node (ref "U3") (pin "11") (pinfunction "PD7(AIN1)_11") (pintype "bidirectional"))
    )
    (net (code "20") (name "D8") (class "Default")
      (node (ref "U1") (pin "D8") (pinfunction "D8_D8") (pintype "bidirectional"))
      (node (ref "U3") (pin "12") (pinfunction "PB0(ICP)_12") (pintype "bidirectional"))
    )
    (net (code "21") (name "D9") (class "Default")
      (node (ref "U1") (pin "D9") (pinfunction "D9_D9") (pintype "bidirectional"))
      (node (ref "U3") (pin "13") (pinfunction "PB1(OC1A)_13") (pintype "bidirectional"))
    )
    (net (code "22") (name "D10{slash}ETHERNER_SS") (class "Default")
      (node (ref "U1") (pin "D10") (pinfunction "D10_D10") (pintype "bidirectional"))
      (node (ref "U3") (pin "14") (pinfunction "PB2(SS/OC1B)_14") (pintype "bidirectional"))
    )
    (net (code "23") (name "D11{slash}MOSI") (class "Default")
      (node (ref "U1") (pin "D11") (pinfunction "D11_D11") (pintype "bidirectional"))
      (node (ref "U1") (pin "MOSI") (pinfunction "MOSI_MOSI") (pintype "bidirectional"))
      (node (ref "U3") (pin "15") (pinfunction "PB3(MOSI/OC2)_15") (pintype "bidirectional"))
    )
    (net (code "24") (name "D12{slash}MISO") (class "Default")
      (node (ref "U1") (pin "D12") (pinfunction "D12_D12") (pintype "bidirectional"))
      (node (ref "U1") (pin "MISO") (pinfunction "MISO_MISO") (pintype "bidirectional"))
      (node (ref "U3") (pin "16") (pinfunction "PB4(MISO)_16") (pintype "bidirectional"))
    )
    (net (code "25") (name "D13{slash}SCK") (class "Default")
      (node (ref "U1") (pin "D13") (pinfunction "D13_D13") (pintype "bidirectional"))
      (node (ref "U1") (pin "SCK") (pinfunction "SCK_SCK") (pintype "bidirectional"))
      (node (ref "U3") (pin "17") (pinfunction "PB5(SCK)_17") (pintype "bidirectional"))
    )
    (net (code "26") (name "DTR") (class "Default")
      (node (ref "C29") (pin "2") (pinfunction "2_2") (pintype "passive"))
      (node (ref "JP6") (pin "6") (pinfunction "6_6") (pintype "passive"))
    )
    (net (code "27") (name "FTDI_PWR") (class "Default")
      (node (ref "C38") (pin "2") (pinfunction "2_2") (pintype "passive"))
      (node (ref "JP6") (pin "3") (pinfunction "3_3") (pintype "passive"))
      (node (ref "SJ9") (pin "1") (pinfunction "1_1") (pintype "passive"))
    )
    (net (code "28") (name "GND") (class "Default")
      (node (ref "C1") (pin "1") (pinfunction "1_1") (pintype "passive"))
      (node (ref "C10") (pin "2") (pinfunction "2_2") (pintype "passive"))
      (node (ref "C11") (pin "2") (pinfunction "2_2") (pintype "passive"))
      (node (ref "C12") (pin "-") (pinfunction "-_-") (pintype "passive"))
      (node (ref "C13") (pin "2") (pinfunction "2_2") (pintype "passive"))
      (node (ref "C2") (pin "2") (pinfunction "2_2") (pintype "passive"))
      (node (ref "C3") (pin "1") (pinfunction "1_1") (pintype "passive"))
      (node (ref "C38") (pin "1") (pinfunction "1_1") (pintype "passive"))
      (node (ref "C4") (pin "2") (pinfunction "2_2") (pintype "passive"))
      (node (ref "C5") (pin "2") (pinfunction "2_2") (pintype "passive"))
      (node (ref "C6") (pin "1") (pinfunction "1_1") (pintype "passive"))
      (node (ref "C7") (pin "-") (pinfunction "-_-") (pintype "passive"))
      (node (ref "C8") (pin "-") (pinfunction "-_-") (pintype "passive"))
      (node (ref "C9") (pin "2") (pinfunction "2_2") (pintype "passive"))
      (node (ref "IC1") (pin "2") (pinfunction "A1_2") (pintype "bidirectional"))
      (node (ref "IC1") (pin "3") (pinfunction "A2_3") (pintype "bidirectional"))
      (node (ref "IC1") (pin "8") (pinfunction "GND_8") (pintype "bidirectional"))
      (node (ref "IC2") (pin "1") (pinfunction "A0_1") (pintype "bidirectional"))
      (node (ref "IC2") (pin "2") (pinfunction "A1_2") (pintype "bidirectional"))
      (node (ref "IC2") (pin "3") (pinfunction "A2_3") (pintype "bidirectional"))
      (node (ref "IC2") (pin "8") (pinfunction "GND_8") (pintype "bidirectional"))
      (node (ref "IC3") (pin "1") (pinfunction "A0_1") (pintype "bidirectional"))
      (node (ref "IC3") (pin "3") (pinfunction "A2_3") (pintype "bidirectional"))
      (node (ref "IC3") (pin "8") (pinfunction "GND_8") (pintype "bidirectional"))
      (node (ref "IC4") (pin "3") (pinfunction "A2_3") (pintype "bidirectional"))
      (node (ref "IC4") (pin "8") (pinfunction "GND_8") (pintype "bidirectional"))
      (node (ref "JP14") (pin "4") (pinfunction "4_4") (pintype "passive"))
      (node (ref "JP2") (pin "2") (pinfunction "2_2") (pintype "passive"))
      (node (ref "JP6") (pin "1") (pinfunction "1_1") (pintype "passive"))
      (node (ref "JP6") (pin "2") (pinfunction "2_2") (pintype "passive"))
      (node (ref "Q1") (pin "2") (pinfunction "2_2") (pintype "passive"))
      (node (ref "Q10") (pin "2") (pinfunction "S_2") (pintype "bidirectional"))
      (node (ref "Q11") (pin "2") (pinfunction "S_2") (pintype "bidirectional"))
      (node (ref "Q12") (pin "2") (pinfunction "S_2") (pintype "bidirectional"))
      (node (ref "Q13") (pin "2") (pinfunction "S_2") (pintype "bidirectional"))
      (node (ref "Q14") (pin "2") (pinfunction "S_2") (pintype "bidirectional"))
      (node (ref "Q15") (pin "2") (pinfunction "S_2") (pintype "bidirectional"))
      (node (ref "Q16") (pin "2") (pinfunction "S_2") (pintype "bidirectional"))
      (node (ref "Q17") (pin "2") (pinfunction "S_2") (pintype "bidirectional"))
      (node (ref "Q18") (pin "2") (pinfunction "S_2") (pintype "bidirectional"))
      (node (ref "Q19") (pin "2") (pinfunction "S_2") (pintype "bidirectional"))
      (node (ref "Q2") (pin "2") (pinfunction "S_2") (pintype "bidirectional"))
      (node (ref "Q20") (pin "2") (pinfunction "S_2") (pintype "bidirectional"))
      (node (ref "Q21") (pin "2") (pinfunction "S_2") (pintype "bidirectional"))
      (node (ref "Q22") (pin "2") (pinfunction "S_2") (pintype "bidirectional"))
      (node (ref "Q23") (pin "2") (pinfunction "S_2") (pintype "bidirectional"))
      (node (ref "Q24") (pin "2") (pinfunction "S_2") (pintype "bidirectional"))
      (node (ref "Q25") (pin "2") (pinfunction "S_2") (pintype "bidirectional"))
      (node (ref "Q3") (pin "2") (pinfunction "S_2") (pintype "bidirectional"))
      (node (ref "Q4") (pin "2") (pinfunction "S_2") (pintype "bidirectional"))
      (node (ref "Q5") (pin "2") (pinfunction "S_2") (pintype "bidirectional"))
      (node (ref "Q6") (pin "2") (pinfunction "S_2") (pintype "bidirectional"))
      (node (ref "Q7") (pin "2") (pinfunction "S_2") (pintype "bidirectional"))
      (node (ref "Q8") (pin "2") (pinfunction "S_2") (pintype "bidirectional"))
      (node (ref "Q9") (pin "2") (pinfunction "S_2") (pintype "bidirectional"))
      (node (ref "R1") (pin "1") (pinfunction "1_1") (pintype "passive"))
      (node (ref "R10") (pin "1") (pinfunction "1_1") (pintype "passive"))
      (node (ref "R11") (pin "1") (pinfunction "1_1") (pintype "passive"))
      (node (ref "R12") (pin "1") (pinfunction "1_1") (pintype "passive"))
      (node (ref "R13") (pin "1") (pinfunction "1_1") (pintype "passive"))
      (node (ref "R14") (pin "1") (pinfunction "1_1") (pintype "passive"))
      (node (ref "R15") (pin "1") (pinfunction "1_1") (pintype "passive"))
      (node (ref "R16") (pin "1") (pinfunction "1_1") (pintype "passive"))
      (node (ref "R17") (pin "1") (pinfunction "1_1") (pintype "passive"))
      (node (ref "R18") (pin "1") (pinfunction "1_1") (pintype "passive"))
      (node (ref "R19") (pin "1") (pinfunction "1_1") (pintype "passive"))
      (node (ref "R2") (pin "1") (pinfunction "1_1") (pintype "passive"))
      (node (ref "R20") (pin "1") (pinfunction "1_1") (pintype "passive"))
      (node (ref "R21") (pin "1") (pinfunction "1_1") (pintype "passive"))
      (node (ref "R22") (pin "1") (pinfunction "1_1") (pintype "passive"))
      (node (ref "R23") (pin "1") (pinfunction "1_1") (pintype "passive"))
      (node (ref "R24") (pin "1") (pinfunction "1_1") (pintype "passive"))
      (node (ref "R25") (pin "1") (pinfunction "1_1") (pintype "passive"))
      (node (ref "R4") (pin "1") (pinfunction "1_1") (pintype "passive"))
      (node (ref "R5") (pin "1") (pinfunction "1_1") (pintype "passive"))
      (node (ref "R6") (pin "1") (pinfunction "1_1") (pintype "passive"))
      (node (ref "R60") (pin "2") (pinfunction "2_2") (pintype "passive"))
      (node (ref "R61") (pin "2") (pinfunction "2_2") (pintype "passive"))
      (node (ref "R62") (pin "2") (pinfunction "2_2") (pintype "passive"))
      (node (ref "R63") (pin "2") (pinfunction "2_2") (pintype "passive"))
      (node (ref "R7") (pin "1") (pinfunction "1_1") (pintype "passive"))
      (node (ref "R8") (pin "1") (pinfunction "1_1") (pintype "passive"))
      (node (ref "R9") (pin "1") (pinfunction "1_1") (pintype "passive"))
      (node (ref "U1") (pin "GND@1") (pinfunction "GND_GND@1") (pintype "power_in"))
      (node (ref "U1") (pin "GND@2") (pinfunction "GND_GND@2") (pintype "power_in"))
      (node (ref "U1") (pin "GND@3") (pinfunction "GND_GND@3") (pintype "power_in"))
      (node (ref "U1") (pin "GND@ISP") (pinfunction "GND_GND@ISP") (pintype "power_in"))
      (node (ref "U2") (pin "2") (pinfunction "GND_2") (pintype "bidirectional"))
      (node (ref "U3") (pin "21") (pinfunction "AGND_21") (pintype "bidirectional"))
      (node (ref "U3") (pin "3") (pinfunction "GND_3") (pintype "bidirectional"))
      (node (ref "U3") (pin "5") (pinfunction "GND_5") (pintype "bidirectional"))
      (node (ref "U3") (pin "PAD") (pinfunction "GND_PAD") (pintype "bidirectional"))
      (node (ref "U4") (pin "2") (pinfunction "GND_2") (pintype "bidirectional"))
    )
    (net (code "29") (name "I0") (class "Default")
      (node (ref "IC4") (pin "4") (pinfunction "P0_4") (pintype "bidirectional"))
      (node (ref "JP15") (pin "3") (pinfunction "3_3") (pintype "passive"))
      (node (ref "R26") (pin "1") (pinfunction "1_1") (pintype "passive"))
    )
    (net (code "30") (name "I1") (class "Default")
      (node (ref "IC4") (pin "5") (pinfunction "P1_5") (pintype "bidirectional"))
      (node (ref "JP15") (pin "2") (pinfunction "2_2") (pintype "passive"))
      (node (ref "R27") (pin "1") (pinfunction "1_1") (pintype "passive"))
    )
    (net (code "31") (name "I2") (class "Default")
      (node (ref "IC4") (pin "6") (pinfunction "P2_6") (pintype "bidirectional"))
      (node (ref "JP15") (pin "1") (pinfunction "1_1") (pintype "passive"))
      (node (ref "R28") (pin "1") (pinfunction "1_1") (pintype "passive"))
    )
    (net (code "32") (name "I3") (class "Default")
      (node (ref "IC4") (pin "7") (pinfunction "P3_7") (pintype "bidirectional"))
      (node (ref "JP16") (pin "3") (pinfunction "3_3") (pintype "passive"))
      (node (ref "R29") (pin "1") (pinfunction "1_1") (pintype "passive"))
    )
    (net (code "33") (name "I4") (class "Default")
      (node (ref "IC4") (pin "9") (pinfunction "P4_9") (pintype "bidirectional"))
      (node (ref "JP16") (pin "2") (pinfunction "2_2") (pintype "passive"))
      (node (ref "R30") (pin "1") (pinfunction "1_1") (pintype "passive"))
    )
    (net (code "34") (name "I5") (class "Default")
      (node (ref "IC4") (pin "10") (pinfunction "P5_10") (pintype "bidirectional"))
      (node (ref "JP16") (pin "1") (pinfunction "1_1") (pintype "passive"))
      (node (ref "R35") (pin "1") (pinfunction "1_1") (pintype "passive"))
    )
    (net (code "35") (name "I6") (class "Default")
      (node (ref "IC4") (pin "11") (pinfunction "P6_11") (pintype "bidirectional"))
      (node (ref "JP17") (pin "2") (pinfunction "2_2") (pintype "passive"))
      (node (ref "R33") (pin "1") (pinfunction "1_1") (pintype "passive"))
    )
    (net (code "36") (name "I7") (class "Default")
      (node (ref "IC4") (pin "12") (pinfunction "P7_12") (pintype "bidirectional"))
      (node (ref "JP17") (pin "1") (pinfunction "1_1") (pintype "passive"))
      (node (ref "R34") (pin "1") (pinfunction "1_1") (pintype "passive"))
    )
    (net (code "37") (name "Net-(LED1-PadA)") (class "Default")
      (node (ref "LED1") (pin "A") (pinfunction "A_A") (pintype "passive"))
      (node (ref "R36") (pin "1") (pinfunction "1_1") (pintype "passive"))
    )
    (net (code "38") (name "Net-(LED2-PadA)") (class "Default")
      (node (ref "LED2") (pin "A") (pinfunction "A_A") (pintype "passive"))
      (node (ref "R37") (pin "1") (pinfunction "1_1") (pintype "passive"))
    )
    (net (code "39") (name "Net-(LED3-PadA)") (class "Default")
      (node (ref "LED3") (pin "A") (pinfunction "A_A") (pintype "passive"))
      (node (ref "R38") (pin "1") (pinfunction "1_1") (pintype "passive"))
    )
    (net (code "40") (name "Net-(LED4-PadA)") (class "Default")
      (node (ref "LED4") (pin "A") (pinfunction "A_A") (pintype "passive"))
      (node (ref "R39") (pin "1") (pinfunction "1_1") (pintype "passive"))
    )
    (net (code "41") (name "Net-(LED5-PadA)") (class "Default")
      (node (ref "LED5") (pin "A") (pinfunction "A_A") (pintype "passive"))
      (node (ref "R40") (pin "1") (pinfunction "1_1") (pintype "passive"))
    )
    (net (code "42") (name "Net-(LED6-PadA)") (class "Default")
      (node (ref "LED6") (pin "A") (pinfunction "A_A") (pintype "passive"))
      (node (ref "R41") (pin "1") (pinfunction "1_1") (pintype "passive"))
    )
    (net (code "43") (name "Net-(LED7-PadA)") (class "Default")
      (node (ref "LED7") (pin "A") (pinfunction "A_A") (pintype "passive"))
      (node (ref "R42") (pin "1") (pinfunction "1_1") (pintype "passive"))
    )
    (net (code "44") (name "Net-(LED8-PadA)") (class "Default")
      (node (ref "LED8") (pin "A") (pinfunction "A_A") (pintype "passive"))
      (node (ref "R43") (pin "1") (pinfunction "1_1") (pintype "passive"))
    )
    (net (code "45") (name "Net-(LED9-PadA)") (class "Default")
      (node (ref "LED9") (pin "A") (pinfunction "A_A") (pintype "passive"))
      (node (ref "R44") (pin "1") (pinfunction "1_1") (pintype "passive"))
    )
    (net (code "46") (name "Net-(LED10-PadA)") (class "Default")
      (node (ref "LED10") (pin "A") (pinfunction "A_A") (pintype "passive"))
      (node (ref "R45") (pin "1") (pinfunction "1_1") (pintype "passive"))
    )
    (net (code "47") (name "Net-(LED11-PadA)") (class "Default")
      (node (ref "LED11") (pin "A") (pinfunction "A_A") (pintype "passive"))
      (node (ref "R46") (pin "1") (pinfunction "1_1") (pintype "passive"))
    )
    (net (code "48") (name "Net-(LED12-PadA)") (class "Default")
      (node (ref "LED12") (pin "A") (pinfunction "A_A") (pintype "passive"))
      (node (ref "R47") (pin "1") (pinfunction "1_1") (pintype "passive"))
    )
    (net (code "49") (name "Net-(LED13-PadA)") (class "Default")
      (node (ref "LED13") (pin "A") (pinfunction "A_A") (pintype "passive"))
      (node (ref "R48") (pin "1") (pinfunction "1_1") (pintype "passive"))
    )
    (net (code "50") (name "Net-(LED14-PadA)") (class "Default")
      (node (ref "LED14") (pin "A") (pinfunction "A_A") (pintype "passive"))
      (node (ref "R49") (pin "1") (pinfunction "1_1") (pintype "passive"))
    )
    (net (code "51") (name "Net-(LED15-PadA)") (class "Default")
      (node (ref "LED15") (pin "A") (pinfunction "A_A") (pintype "passive"))
      (node (ref "R50") (pin "1") (pinfunction "1_1") (pintype "passive"))
    )
    (net (code "52") (name "Net-(LED16-PadA)") (class "Default")
      (node (ref "LED16") (pin "A") (pinfunction "A_A") (pintype "passive"))
      (node (ref "R51") (pin "1") (pinfunction "1_1") (pintype "passive"))
    )
    (net (code "53") (name "Net-(LED17-PadA)") (class "Default")
      (node (ref "LED17") (pin "A") (pinfunction "A_A") (pintype "passive"))
      (node (ref "R52") (pin "1") (pinfunction "1_1") (pintype "passive"))
    )
    (net (code "54") (name "Net-(LED18-PadA)") (class "Default")
      (node (ref "LED18") (pin "A") (pinfunction "A_A") (pintype "passive"))
      (node (ref "R53") (pin "1") (pinfunction "1_1") (pintype "passive"))
    )
    (net (code "55") (name "Net-(LED19-PadA)") (class "Default")
      (node (ref "LED19") (pin "A") (pinfunction "A_A") (pintype "passive"))
      (node (ref "R54") (pin "1") (pinfunction "1_1") (pintype "passive"))
    )
    (net (code "56") (name "Net-(LED20-PadA)") (class "Default")
      (node (ref "LED20") (pin "A") (pinfunction "A_A") (pintype "passive"))
      (node (ref "R55") (pin "1") (pinfunction "1_1") (pintype "passive"))
    )
    (net (code "57") (name "Net-(LED21-PadA)") (class "Default")
      (node (ref "LED21") (pin "A") (pinfunction "A_A") (pintype "passive"))
      (node (ref "R56") (pin "1") (pinfunction "1_1") (pintype "passive"))
    )
    (net (code "58") (name "Net-(LED22-PadA)") (class "Default")
      (node (ref "LED22") (pin "A") (pinfunction "A_A") (pintype "passive"))
      (node (ref "R57") (pin "1") (pinfunction "1_1") (pintype "passive"))
    )
    (net (code "59") (name "Net-(LED23-PadA)") (class "Default")
      (node (ref "LED23") (pin "A") (pinfunction "A_A") (pintype "passive"))
      (node (ref "R58") (pin "1") (pinfunction "1_1") (pintype "passive"))
    )
    (net (code "60") (name "Net-(LED24-PadA)") (class "Default")
      (node (ref "LED24") (pin "A") (pinfunction "A_A") (pintype "passive"))
      (node (ref "R59") (pin "1") (pinfunction "1_1") (pintype "passive"))
    )
    (net (code "61") (name "Net-(LED25-PadC)") (class "Default")
      (node (ref "LED25") (pin "C") (pinfunction "C_C") (pintype "passive"))
      (node (ref "R60") (pin "1") (pinfunction "1_1") (pintype "passive"))
    )
    (net (code "62") (name "Net-(LED26-PadC)") (class "Default")
      (node (ref "LED26") (pin "C") (pinfunction "C_C") (pintype "passive"))
      (node (ref "R61") (pin "1") (pinfunction "1_1") (pintype "passive"))
    )
    (net (code "63") (name "Net-(LED27-PadC)") (class "Default")
      (node (ref "LED27") (pin "C") (pinfunction "C_C") (pintype "passive"))
      (node (ref "R62") (pin "1") (pinfunction "1_1") (pintype "passive"))
    )
    (net (code "64") (name "Net-(LED28-PadC)") (class "Default")
      (node (ref "LED28") (pin "C") (pinfunction "C_C") (pintype "passive"))
      (node (ref "R63") (pin "1") (pinfunction "1_1") (pintype "passive"))
    )
    (net (code "65") (name "Net-(U3-PB6(XTAL1{slash}TOSC1))") (class "Default")
      (node (ref "Q1") (pin "1") (pinfunction "1_1") (pintype "passive"))
      (node (ref "U3") (pin "7") (pinfunction "PB6(XTAL1/TOSC1)_7") (pintype "bidirectional"))
    )
    (net (code "66") (name "Net-(U3-PB7(XTAL2{slash}TOSC2))") (class "Default")
      (node (ref "Q1") (pin "3") (pinfunction "3_3") (pintype "passive"))
      (node (ref "U3") (pin "8") (pinfunction "PB7(XTAL2/TOSC2)_8") (pintype "bidirectional"))
    )
    (net (code "67") (name "P0") (class "Default")
      (node (ref "IC2") (pin "4") (pinfunction "P0_4") (pintype "bidirectional"))
      (node (ref "LED1") (pin "C") (pinfunction "C_C") (pintype "passive"))
      (node (ref "Q3") (pin "1") (pinfunction "G_1") (pintype "bidirectional"))
      (node (ref "R4") (pin "2") (pinfunction "2_2") (pintype "passive"))
    )
    (net (code "68") (name "P1") (class "Default")
      (node (ref "IC2") (pin "5") (pinfunction "P1_5") (pintype "bidirectional"))
      (node (ref "LED2") (pin "C") (pinfunction "C_C") (pintype "passive"))
      (node (ref "Q2") (pin "1") (pinfunction "G_1") (pintype "bidirectional"))
      (node (ref "R1") (pin "2") (pinfunction "2_2") (pintype "passive"))
    )
    (net (code "69") (name "P2") (class "Default")
      (node (ref "IC2") (pin "6") (pinfunction "P2_6") (pintype "bidirectional"))
      (node (ref "LED3") (pin "C") (pinfunction "C_C") (pintype "passive"))
      (node (ref "Q4") (pin "1") (pinfunction "G_1") (pintype "bidirectional"))
      (node (ref "R2") (pin "2") (pinfunction "2_2") (pintype "passive"))
    )
    (net (code "70") (name "P3") (class "Default")
      (node (ref "IC2") (pin "7") (pinfunction "P3_7") (pintype "bidirectional"))
      (node (ref "LED4") (pin "C") (pinfunction "C_C") (pintype "passive"))
      (node (ref "Q5") (pin "1") (pinfunction "G_1") (pintype "bidirectional"))
      (node (ref "R5") (pin "2") (pinfunction "2_2") (pintype "passive"))
    )
    (net (code "71") (name "P4") (class "Default")
      (node (ref "IC2") (pin "9") (pinfunction "P4_9") (pintype "bidirectional"))
      (node (ref "LED5") (pin "C") (pinfunction "C_C") (pintype "passive"))
      (node (ref "Q6") (pin "1") (pinfunction "G_1") (pintype "bidirectional"))
      (node (ref "R6") (pin "2") (pinfunction "2_2") (pintype "passive"))
    )
    (net (code "72") (name "P5") (class "Default")
      (node (ref "IC2") (pin "10") (pinfunction "P5_10") (pintype "bidirectional"))
      (node (ref "LED6") (pin "C") (pinfunction "C_C") (pintype "passive"))
      (node (ref "Q7") (pin "1") (pinfunction "G_1") (pintype "bidirectional"))
      (node (ref "R7") (pin "2") (pinfunction "2_2") (pintype "passive"))
    )
    (net (code "73") (name "P6") (class "Default")
      (node (ref "IC2") (pin "11") (pinfunction "P6_11") (pintype "bidirectional"))
      (node (ref "LED7") (pin "C") (pinfunction "C_C") (pintype "passive"))
      (node (ref "Q8") (pin "1") (pinfunction "G_1") (pintype "bidirectional"))
      (node (ref "R8") (pin "2") (pinfunction "2_2") (pintype "passive"))
    )
    (net (code "74") (name "P7") (class "Default")
      (node (ref "IC2") (pin "12") (pinfunction "P7_12") (pintype "bidirectional"))
      (node (ref "LED8") (pin "C") (pinfunction "C_C") (pintype "passive"))
      (node (ref "Q9") (pin "1") (pinfunction "G_1") (pintype "bidirectional"))
      (node (ref "R9") (pin "2") (pinfunction "2_2") (pintype "passive"))
    )
    (net (code "75") (name "P8") (class "Default")
      (node (ref "IC1") (pin "4") (pinfunction "P0_4") (pintype "bidirectional"))
      (node (ref "LED9") (pin "C") (pinfunction "C_C") (pintype "passive"))
      (node (ref "Q10") (pin "1") (pinfunction "G_1") (pintype "bidirectional"))
      (node (ref "R10") (pin "2") (pinfunction "2_2") (pintype "passive"))
    )
    (net (code "76") (name "P9") (class "Default")
      (node (ref "IC1") (pin "5") (pinfunction "P1_5") (pintype "bidirectional"))
      (node (ref "LED10") (pin "C") (pinfunction "C_C") (pintype "passive"))
      (node (ref "Q11") (pin "1") (pinfunction "G_1") (pintype "bidirectional"))
      (node (ref "R11") (pin "2") (pinfunction "2_2") (pintype "passive"))
    )
    (net (code "77") (name "P10") (class "Default")
      (node (ref "IC1") (pin "6") (pinfunction "P2_6") (pintype "bidirectional"))
      (node (ref "LED11") (pin "C") (pinfunction "C_C") (pintype "passive"))
      (node (ref "Q12") (pin "1") (pinfunction "G_1") (pintype "bidirectional"))
      (node (ref "R12") (pin "2") (pinfunction "2_2") (pintype "passive"))
    )
    (net (code "78") (name "P11") (class "Default")
      (node (ref "IC1") (pin "7") (pinfunction "P3_7") (pintype "bidirectional"))
      (node (ref "LED12") (pin "C") (pinfunction "C_C") (pintype "passive"))
      (node (ref "Q13") (pin "1") (pinfunction "G_1") (pintype "bidirectional"))
      (node (ref "R13") (pin "2") (pinfunction "2_2") (pintype "passive"))
    )
    (net (code "79") (name "P12") (class "Default")
      (node (ref "IC1") (pin "9") (pinfunction "P4_9") (pintype "bidirectional"))
      (node (ref "LED13") (pin "C") (pinfunction "C_C") (pintype "passive"))
      (node (ref "Q14") (pin "1") (pinfunction "G_1") (pintype "bidirectional"))
      (node (ref "R14") (pin "2") (pinfunction "2_2") (pintype "passive"))
    )
    (net (code "80") (name "P13") (class "Default")
      (node (ref "IC1") (pin "10") (pinfunction "P5_10") (pintype "bidirectional"))
      (node (ref "LED14") (pin "C") (pinfunction "C_C") (pintype "passive"))
      (node (ref "Q15") (pin "1") (pinfunction "G_1") (pintype "bidirectional"))
      (node (ref "R15") (pin "2") (pinfunction "2_2") (pintype "passive"))
    )
    (net (code "81") (name "P14") (class "Default")
      (node (ref "IC1") (pin "11") (pinfunction "P6_11") (pintype "bidirectional"))
      (node (ref "LED15") (pin "C") (pinfunction "C_C") (pintype "passive"))
      (node (ref "Q16") (pin "1") (pinfunction "G_1") (pintype "bidirectional"))
      (node (ref "R16") (pin "2") (pinfunction "2_2") (pintype "passive"))
    )
    (net (code "82") (name "P15") (class "Default")
      (node (ref "IC1") (pin "12") (pinfunction "P7_12") (pintype "bidirectional"))
      (node (ref "LED16") (pin "C") (pinfunction "C_C") (pintype "passive"))
      (node (ref "Q17") (pin "1") (pinfunction "G_1") (pintype "bidirectional"))
      (node (ref "R17") (pin "2") (pinfunction "2_2") (pintype "passive"))
    )
    (net (code "83") (name "P16") (class "Default")
      (node (ref "IC3") (pin "4") (pinfunction "P0_4") (pintype "bidirectional"))
      (node (ref "LED17") (pin "C") (pinfunction "C_C") (pintype "passive"))
      (node (ref "Q18") (pin "1") (pinfunction "G_1") (pintype "bidirectional"))
      (node (ref "R18") (pin "2") (pinfunction "2_2") (pintype "passive"))
    )
    (net (code "84") (name "P17") (class "Default")
      (node (ref "IC3") (pin "5") (pinfunction "P1_5") (pintype "bidirectional"))
      (node (ref "LED18") (pin "C") (pinfunction "C_C") (pintype "passive"))
      (node (ref "Q19") (pin "1") (pinfunction "G_1") (pintype "bidirectional"))
      (node (ref "R19") (pin "2") (pinfunction "2_2") (pintype "passive"))
    )
    (net (code "85") (name "P18") (class "Default")
      (node (ref "IC3") (pin "6") (pinfunction "P2_6") (pintype "bidirectional"))
      (node (ref "LED19") (pin "C") (pinfunction "C_C") (pintype "passive"))
      (node (ref "Q20") (pin "1") (pinfunction "G_1") (pintype "bidirectional"))
      (node (ref "R20") (pin "2") (pinfunction "2_2") (pintype "passive"))
    )
    (net (code "86") (name "P19") (class "Default")
      (node (ref "IC3") (pin "7") (pinfunction "P3_7") (pintype "bidirectional"))
      (node (ref "LED20") (pin "C") (pinfunction "C_C") (pintype "passive"))
      (node (ref "Q21") (pin "1") (pinfunction "G_1") (pintype "bidirectional"))
      (node (ref "R21") (pin "2") (pinfunction "2_2") (pintype "passive"))
    )
    (net (code "87") (name "P20") (class "Default")
      (node (ref "IC3") (pin "9") (pinfunction "P4_9") (pintype "bidirectional"))
      (node (ref "LED21") (pin "C") (pinfunction "C_C") (pintype "passive"))
      (node (ref "Q22") (pin "1") (pinfunction "G_1") (pintype "bidirectional"))
      (node (ref "R22") (pin "2") (pinfunction "2_2") (pintype "passive"))
    )
    (net (code "88") (name "P21") (class "Default")
      (node (ref "IC3") (pin "10") (pinfunction "P5_10") (pintype "bidirectional"))
      (node (ref "LED22") (pin "C") (pinfunction "C_C") (pintype "passive"))
      (node (ref "Q23") (pin "1") (pinfunction "G_1") (pintype "bidirectional"))
      (node (ref "R23") (pin "2") (pinfunction "2_2") (pintype "passive"))
    )
    (net (code "89") (name "P22") (class "Default")
      (node (ref "IC3") (pin "11") (pinfunction "P6_11") (pintype "bidirectional"))
      (node (ref "LED23") (pin "C") (pinfunction "C_C") (pintype "passive"))
      (node (ref "Q24") (pin "1") (pinfunction "G_1") (pintype "bidirectional"))
      (node (ref "R24") (pin "2") (pinfunction "2_2") (pintype "passive"))
    )
    (net (code "90") (name "P23") (class "Default")
      (node (ref "IC3") (pin "12") (pinfunction "P7_12") (pintype "bidirectional"))
      (node (ref "LED24") (pin "C") (pinfunction "C_C") (pintype "passive"))
      (node (ref "Q25") (pin "1") (pinfunction "G_1") (pintype "bidirectional"))
      (node (ref "R25") (pin "2") (pinfunction "2_2") (pintype "passive"))
    )
    (net (code "91") (name "R0") (class "Default")
      (node (ref "JP1") (pin "3") (pinfunction "3_3") (pintype "passive"))
      (node (ref "Q3") (pin "3") (pinfunction "D_3") (pintype "bidirectional"))
    )
    (net (code "92") (name "R1") (class "Default")
      (node (ref "JP1") (pin "2") (pinfunction "2_2") (pintype "passive"))
      (node (ref "Q2") (pin "3") (pinfunction "D_3") (pintype "bidirectional"))
    )
    (net (code "93") (name "R2") (class "Default")
      (node (ref "JP1") (pin "1") (pinfunction "1_1") (pintype "passive"))
      (node (ref "Q4") (pin "3") (pinfunction "D_3") (pintype "bidirectional"))
    )
    (net (code "94") (name "R3") (class "Default")
      (node (ref "JP3") (pin "3") (pinfunction "3_3") (pintype "passive"))
      (node (ref "Q5") (pin "3") (pinfunction "D_3") (pintype "bidirectional"))
    )
    (net (code "95") (name "R4") (class "Default")
      (node (ref "JP3") (pin "2") (pinfunction "2_2") (pintype "passive"))
      (node (ref "Q6") (pin "3") (pinfunction "D_3") (pintype "bidirectional"))
    )
    (net (code "96") (name "R5") (class "Default")
      (node (ref "JP3") (pin "1") (pinfunction "1_1") (pintype "passive"))
      (node (ref "Q7") (pin "3") (pinfunction "D_3") (pintype "bidirectional"))
    )
    (net (code "97") (name "R6") (class "Default")
      (node (ref "JP5") (pin "3") (pinfunction "3_3") (pintype "passive"))
      (node (ref "Q8") (pin "3") (pinfunction "D_3") (pintype "bidirectional"))
    )
    (net (code "98") (name "R7") (class "Default")
      (node (ref "JP5") (pin "2") (pinfunction "2_2") (pintype "passive"))
      (node (ref "Q9") (pin "3") (pinfunction "D_3") (pintype "bidirectional"))
    )
    (net (code "99") (name "R8") (class "Default")
      (node (ref "JP5") (pin "1") (pinfunction "1_1") (pintype "passive"))
      (node (ref "Q10") (pin "3") (pinfunction "D_3") (pintype "bidirectional"))
    )
    (net (code "100") (name "R9") (class "Default")
      (node (ref "JP8") (pin "3") (pinfunction "3_3") (pintype "passive"))
      (node (ref "Q11") (pin "3") (pinfunction "D_3") (pintype "bidirectional"))
    )
    (net (code "101") (name "R10") (class "Default")
      (node (ref "JP8") (pin "2") (pinfunction "2_2") (pintype "passive"))
      (node (ref "Q12") (pin "3") (pinfunction "D_3") (pintype "bidirectional"))
    )
    (net (code "102") (name "R11") (class "Default")
      (node (ref "JP8") (pin "1") (pinfunction "1_1") (pintype "passive"))
      (node (ref "Q13") (pin "3") (pinfunction "D_3") (pintype "bidirectional"))
    )
    (net (code "103") (name "R12") (class "Default")
      (node (ref "JP10") (pin "3") (pinfunction "3_3") (pintype "passive"))
      (node (ref "Q14") (pin "3") (pinfunction "D_3") (pintype "bidirectional"))
    )
    (net (code "104") (name "R13") (class "Default")
      (node (ref "JP10") (pin "2") (pinfunction "2_2") (pintype "passive"))
      (node (ref "Q15") (pin "3") (pinfunction "D_3") (pintype "bidirectional"))
    )
    (net (code "105") (name "R14") (class "Default")
      (node (ref "JP10") (pin "1") (pinfunction "1_1") (pintype "passive"))
      (node (ref "Q16") (pin "3") (pinfunction "D_3") (pintype "bidirectional"))
    )
    (net (code "106") (name "R15") (class "Default")
      (node (ref "JP11") (pin "3") (pinfunction "3_3") (pintype "passive"))
      (node (ref "Q17") (pin "3") (pinfunction "D_3") (pintype "bidirectional"))
    )
    (net (code "107") (name "R16") (class "Default")
      (node (ref "JP11") (pin "2") (pinfunction "2_2") (pintype "passive"))
      (node (ref "Q18") (pin "3") (pinfunction "D_3") (pintype "bidirectional"))
    )
    (net (code "108") (name "R17") (class "Default")
      (node (ref "JP11") (pin "1") (pinfunction "1_1") (pintype "passive"))
      (node (ref "Q19") (pin "3") (pinfunction "D_3") (pintype "bidirectional"))
    )
    (net (code "109") (name "R18") (class "Default")
      (node (ref "JP12") (pin "3") (pinfunction "3_3") (pintype "passive"))
      (node (ref "Q20") (pin "3") (pinfunction "D_3") (pintype "bidirectional"))
    )
    (net (code "110") (name "R19") (class "Default")
      (node (ref "JP12") (pin "2") (pinfunction "2_2") (pintype "passive"))
      (node (ref "Q21") (pin "3") (pinfunction "D_3") (pintype "bidirectional"))
    )
    (net (code "111") (name "R20") (class "Default")
      (node (ref "JP12") (pin "1") (pinfunction "1_1") (pintype "passive"))
      (node (ref "Q22") (pin "3") (pinfunction "D_3") (pintype "bidirectional"))
    )
    (net (code "112") (name "R21") (class "Default")
      (node (ref "JP13") (pin "3") (pinfunction "3_3") (pintype "passive"))
      (node (ref "Q23") (pin "3") (pinfunction "D_3") (pintype "bidirectional"))
    )
    (net (code "113") (name "R22") (class "Default")
      (node (ref "JP13") (pin "2") (pinfunction "2_2") (pintype "passive"))
      (node (ref "Q24") (pin "3") (pinfunction "D_3") (pintype "bidirectional"))
    )
    (net (code "114") (name "R23") (class "Default")
      (node (ref "JP13") (pin "1") (pinfunction "1_1") (pintype "passive"))
      (node (ref "Q25") (pin "3") (pinfunction "D_3") (pintype "bidirectional"))
    )
    (net (code "116") (name "RESERVED") (class "Default")
      (node (ref "U1") (pin "RESERVED") (pinfunction "RESERVED_RESERVED") (pintype "no_connect"))
    )
    (net (code "117") (name "RX_FTDI") (class "Default")
      (node (ref "JP6") (pin "4") (pinfunction "4_4") (pintype "passive"))
      (node (ref "R32") (pin "1") (pinfunction "1_1") (pintype "passive"))
    )
    (net (code "118") (name "TX_FTDI") (class "Default")
      (node (ref "JP6") (pin "5") (pinfunction "5_5") (pintype "passive"))
      (node (ref "R31") (pin "1") (pinfunction "1_1") (pintype "passive"))
    )
    (net (code "119") (name "VCC") (class "Default")
      (node (ref "C1") (pin "2") (pinfunction "2_2") (pintype "passive"))
      (node (ref "C6") (pin "2") (pinfunction "2_2") (pintype "passive"))
      (node (ref "L1") (pin "2") (pinfunction "2_2") (pintype "passive"))
      (node (ref "R3") (pin "2") (pinfunction "2_2") (pintype "passive"))
      (node (ref "U3") (pin "18") (pinfunction "AVCC_18") (pintype "bidirectional"))
      (node (ref "U3") (pin "4") (pinfunction "VCC_4") (pintype "bidirectional"))
      (node (ref "U3") (pin "6") (pinfunction "VCC_6") (pintype "bidirectional"))
    )
    (net (code "120") (name "VIN") (class "Default")
      (node (ref "C2") (pin "1") (pinfunction "1_1") (pintype "passive"))
      (node (ref "C8") (pin "+") (pinfunction "+_+") (pintype "passive"))
      (node (ref "JP2") (pin "3") (pinfunction "3_3") (pintype "passive"))
      (node (ref "U1") (pin "VIN") (pinfunction "VIN_VIN") (pintype "power_in"))
      (node (ref "U2") (pin "1") (pinfunction "VIN_1") (pintype "bidirectional"))
    )
    (net (code "121") (name "unconnected-(IC1-~{INT}-Pad13)") (class "Default")
      (node (ref "IC1") (pin "13") (pinfunction "~{INT}_13") (pintype "bidirectional"))
    )
    (net (code "122") (name "unconnected-(IC2-~{INT}-Pad13)") (class "Default")
      (node (ref "IC2") (pin "13") (pinfunction "~{INT}_13") (pintype "bidirectional"))
    )
    (net (code "123") (name "unconnected-(IC3-~{INT}-Pad13)") (class "Default")
      (node (ref "IC3") (pin "13") (pinfunction "~{INT}_13") (pintype "bidirectional"))
    )
    (net (code "124") (name "unconnected-(U2-AUX-Pad4)") (class "Default")
      (node (ref "U2") (pin "4") (pinfunction "AUX_4") (pintype "bidirectional"))
    )
    (net (code "125") (name "unconnected-(U4-AUX-Pad4)") (class "Default")
      (node (ref "U4") (pin "4") (pinfunction "AUX_4") (pintype "bidirectional"))
    )
    (net (code "126") (name "~{RESET}") (class "Default")
      (node (ref "C29") (pin "1") (pinfunction "1_1") (pintype "passive"))
      (node (ref "R3") (pin "1") (pinfunction "1_1") (pintype "passive"))
      (node (ref "U1") (pin "!RESET") (pinfunction "~{RESET}_!RESET") (pintype "bidirectional"))
      (node (ref "U1") (pin "!RESET@ISP") (pinfunction "~{RESET}_!RESET@ISP") (pintype "bidirectional"))
      (node (ref "U3") (pin "29") (pinfunction "PC6(/RESET)_29") (pintype "bidirectional"))
    )
  )
)
